# Test.net
KiCad netlist of a schematic drawn in EAGLE
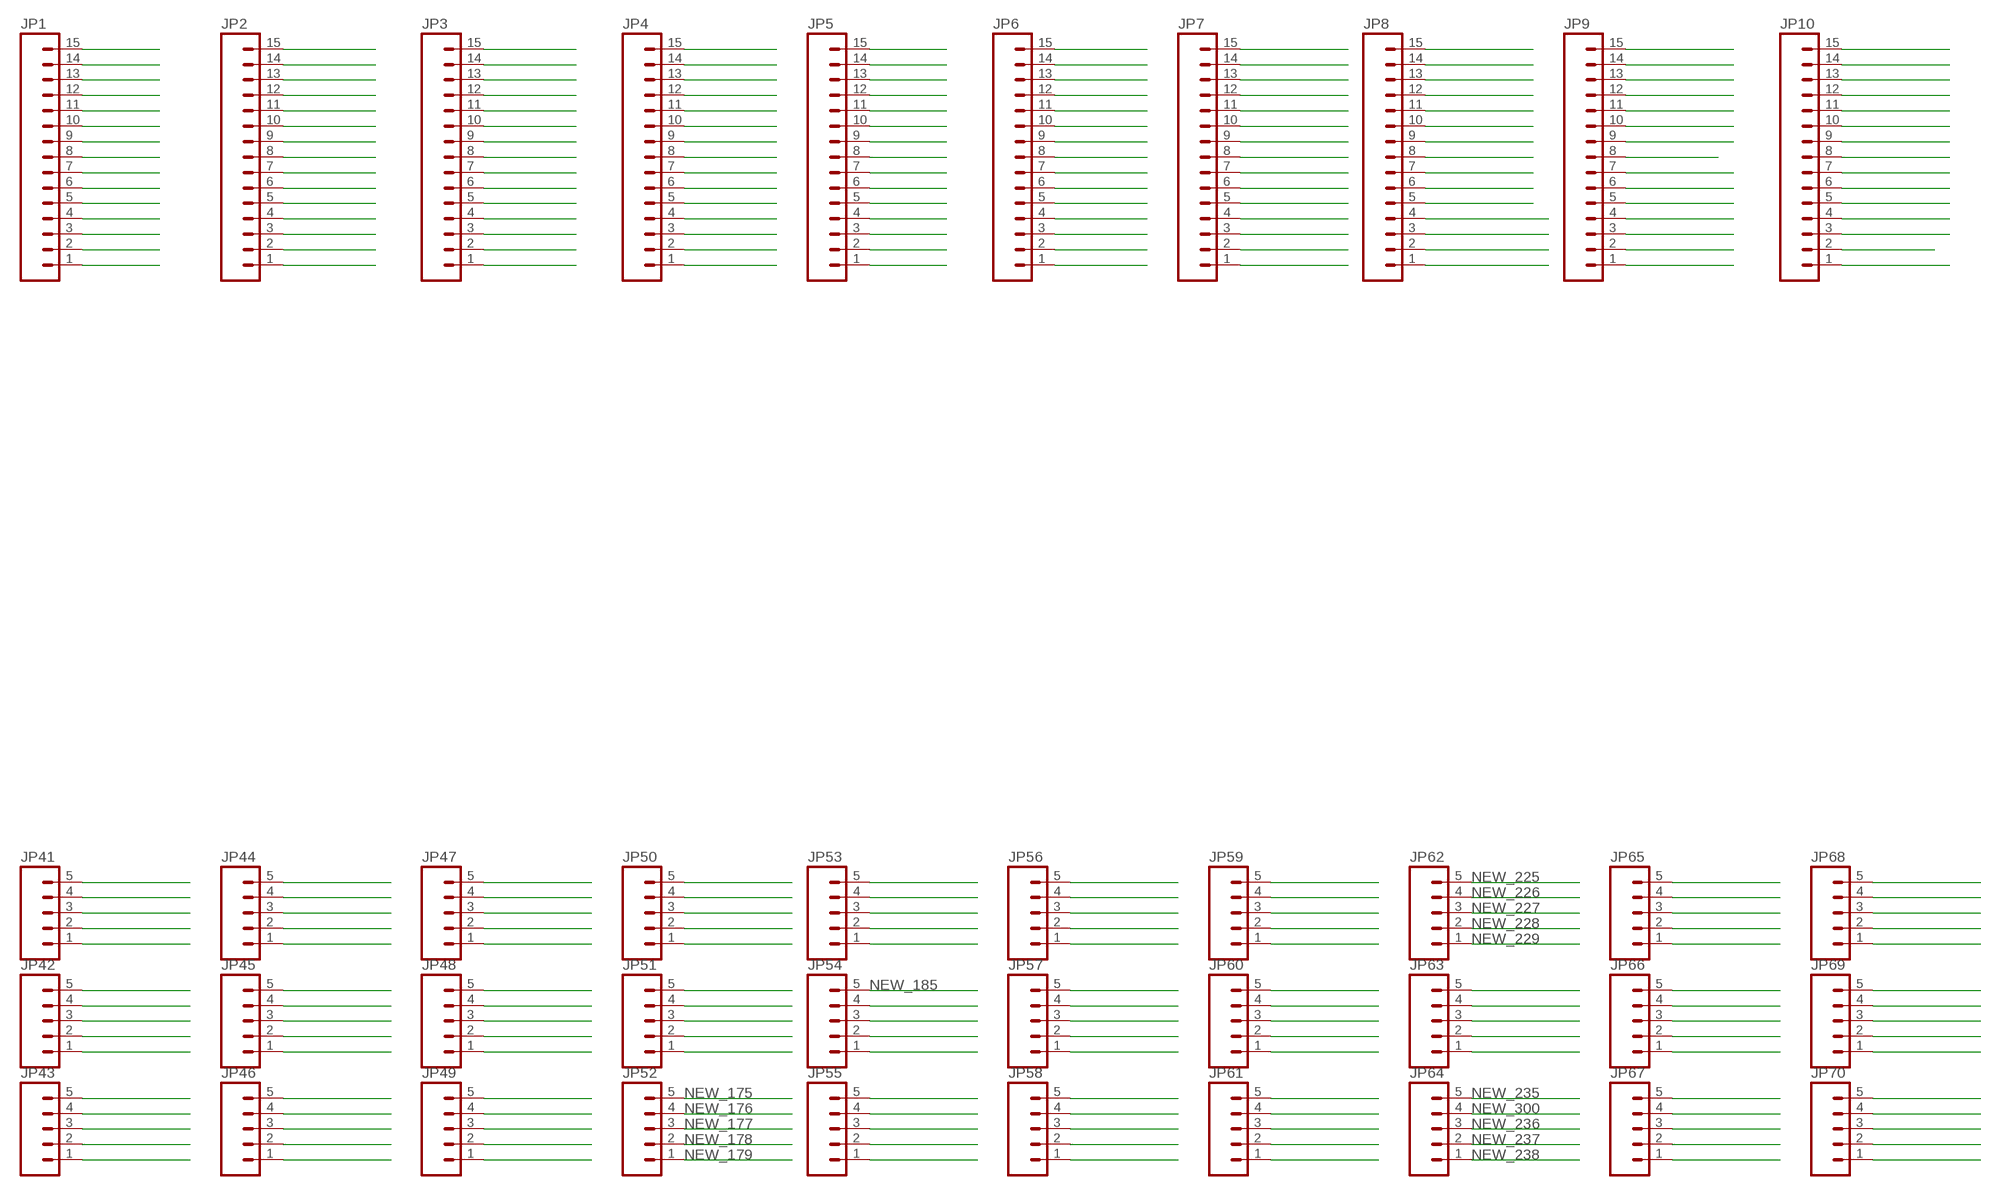
[diagram p0: schematic, sheet 1, part 1 of 2]
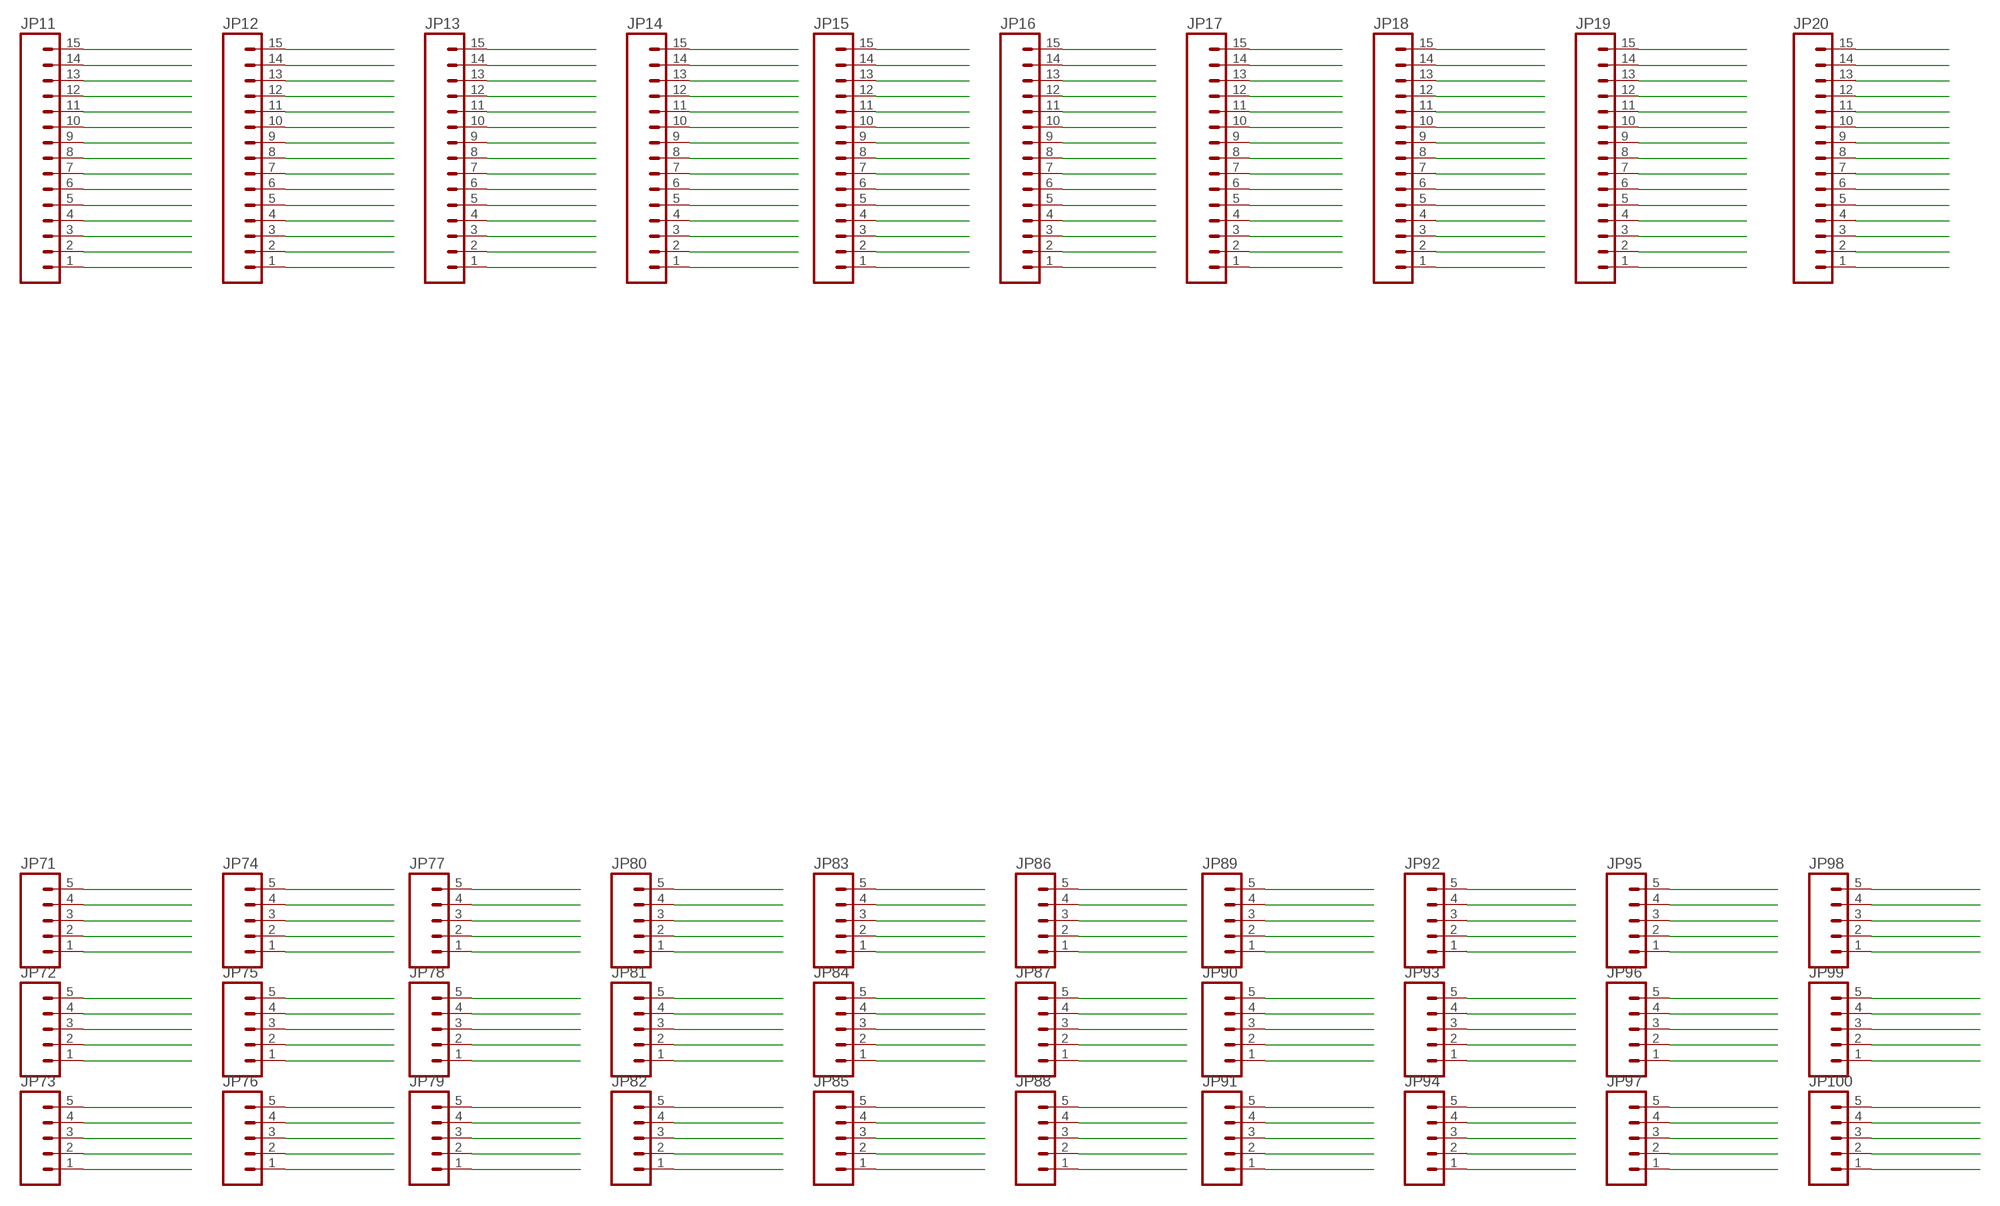
[diagram p1: schematic, sheet 1, part 2 of 2]

(export (version "E")
  (design (tool "Eeschema 10.0.6"))
  (components
    (comp (ref "JP1")
      (value "M15")
      (footprint "eagle-import:1X15")
      (libsource (lib "eagle-import") (part "M15"))
    )
    (comp (ref "JP2")
      (value "M15")
      (footprint "eagle-import:1X15")
      (libsource (lib "eagle-import") (part "M15"))
    )
    (comp (ref "JP3")
      (value "M15")
      (footprint "eagle-import:1X15")
      (libsource (lib "eagle-import") (part "M15"))
    )
    (comp (ref "JP4")
      (value "M15")
      (footprint "eagle-import:1X15")
      (libsource (lib "eagle-import") (part "M15"))
    )
    (comp (ref "JP5")
      (value "M15")
      (footprint "eagle-import:1X15")
      (libsource (lib "eagle-import") (part "M15"))
    )
    (comp (ref "JP6")
      (value "M15")
      (footprint "eagle-import:1X15")
      (libsource (lib "eagle-import") (part "M15"))
    )
    (comp (ref "JP7")
      (value "M15")
      (footprint "eagle-import:1X15")
      (libsource (lib "eagle-import") (part "M15"))
    )
    (comp (ref "JP8")
      (value "M15")
      (footprint "eagle-import:1X15")
      (libsource (lib "eagle-import") (part "M15"))
    )
    (comp (ref "JP9")
      (value "M15")
      (footprint "eagle-import:1X15")
      (libsource (lib "eagle-import") (part "M15"))
    )
    (comp (ref "JP10")
      (value "M15")
      (footprint "eagle-import:1X15")
      (libsource (lib "eagle-import") (part "M15"))
    )
    (comp (ref "JP11")
      (value "M15")
      (footprint "eagle-import:1X15")
      (libsource (lib "eagle-import") (part "M15"))
    )
    (comp (ref "JP12")
      (value "M15")
      (footprint "eagle-import:1X15")
      (libsource (lib "eagle-import") (part "M15"))
    )
    (comp (ref "JP13")
      (value "M15")
      (footprint "eagle-import:1X15")
      (libsource (lib "eagle-import") (part "M15"))
    )
    (comp (ref "JP14")
      (value "M15")
      (footprint "eagle-import:1X15")
      (libsource (lib "eagle-import") (part "M15"))
    )
    (comp (ref "JP15")
      (value "M15")
      (footprint "eagle-import:1X15")
      (libsource (lib "eagle-import") (part "M15"))
    )
    (comp (ref "JP16")
      (value "M15")
      (footprint "eagle-import:1X15")
      (libsource (lib "eagle-import") (part "M15"))
    )
    (comp (ref "JP17")
      (value "M15")
      (footprint "eagle-import:1X15")
      (libsource (lib "eagle-import") (part "M15"))
    )
    (comp (ref "JP18")
      (value "M15")
      (footprint "eagle-import:1X15")
      (libsource (lib "eagle-import") (part "M15"))
    )
    (comp (ref "JP19")
      (value "M15")
      (footprint "eagle-import:1X15")
      (libsource (lib "eagle-import") (part "M15"))
    )
    (comp (ref "JP20")
      (value "M15")
      (footprint "eagle-import:1X15")
      (libsource (lib "eagle-import") (part "M15"))
    )
    (comp (ref "JP41")
      (value "M051.27MM")
      (footprint "eagle-import:1X05-1.27MM")
      (libsource (lib "eagle-import") (part "M051.27MM"))
    )
    (comp (ref "JP42")
      (value "M051.27MM")
      (footprint "eagle-import:1X05-1.27MM")
      (libsource (lib "eagle-import") (part "M051.27MM"))
    )
    (comp (ref "JP43")
      (value "M051.27MM")
      (footprint "eagle-import:1X05-1.27MM")
      (libsource (lib "eagle-import") (part "M051.27MM"))
    )
    (comp (ref "JP44")
      (value "M051.27MM")
      (footprint "eagle-import:1X05-1.27MM")
      (libsource (lib "eagle-import") (part "M051.27MM"))
    )
    (comp (ref "JP45")
      (value "M051.27MM")
      (footprint "eagle-import:1X05-1.27MM")
      (libsource (lib "eagle-import") (part "M051.27MM"))
    )
    (comp (ref "JP46")
      (value "M051.27MM")
      (footprint "eagle-import:1X05-1.27MM")
      (libsource (lib "eagle-import") (part "M051.27MM"))
    )
    (comp (ref "JP47")
      (value "M051.27MM")
      (footprint "eagle-import:1X05-1.27MM")
      (libsource (lib "eagle-import") (part "M051.27MM"))
    )
    (comp (ref "JP48")
      (value "M051.27MM")
      (footprint "eagle-import:1X05-1.27MM")
      (libsource (lib "eagle-import") (part "M051.27MM"))
    )
    (comp (ref "JP49")
      (value "M051.27MM")
      (footprint "eagle-import:1X05-1.27MM")
      (libsource (lib "eagle-import") (part "M051.27MM"))
    )
    (comp (ref "JP50")
      (value "M051.27MM")
      (footprint "eagle-import:1X05-1.27MM")
      (libsource (lib "eagle-import") (part "M051.27MM"))
    )
    (comp (ref "JP51")
      (value "M051.27MM")
      (footprint "eagle-import:1X05-1.27MM")
      (libsource (lib "eagle-import") (part "M051.27MM"))
    )
    (comp (ref "JP52")
      (value "M051.27MM")
      (footprint "eagle-import:1X05-1.27MM")
      (libsource (lib "eagle-import") (part "M051.27MM"))
    )
    (comp (ref "JP53")
      (value "M051.27MM")
      (footprint "eagle-import:1X05-1.27MM")
      (libsource (lib "eagle-import") (part "M051.27MM"))
    )
    (comp (ref "JP54")
      (value "M051.27MM")
      (footprint "eagle-import:1X05-1.27MM")
      (libsource (lib "eagle-import") (part "M051.27MM"))
    )
    (comp (ref "JP55")
      (value "M051.27MM")
      (footprint "eagle-import:1X05-1.27MM")
      (libsource (lib "eagle-import") (part "M051.27MM"))
    )
    (comp (ref "JP56")
      (value "M051.27MM")
      (footprint "eagle-import:1X05-1.27MM")
      (libsource (lib "eagle-import") (part "M051.27MM"))
    )
    (comp (ref "JP57")
      (value "M051.27MM")
      (footprint "eagle-import:1X05-1.27MM")
      (libsource (lib "eagle-import") (part "M051.27MM"))
    )
    (comp (ref "JP58")
      (value "M051.27MM")
      (footprint "eagle-import:1X05-1.27MM")
      (libsource (lib "eagle-import") (part "M051.27MM"))
    )
    (comp (ref "JP59")
      (value "M051.27MM")
      (footprint "eagle-import:1X05-1.27MM")
      (libsource (lib "eagle-import") (part "M051.27MM"))
    )
    (comp (ref "JP60")
      (value "M051.27MM")
      (footprint "eagle-import:1X05-1.27MM")
      (libsource (lib "eagle-import") (part "M051.27MM"))
    )
    (comp (ref "JP61")
      (value "M051.27MM")
      (footprint "eagle-import:1X05-1.27MM")
      (libsource (lib "eagle-import") (part "M051.27MM"))
    )
    (comp (ref "JP62")
      (value "M051.27MM")
      (footprint "eagle-import:1X05-1.27MM")
      (libsource (lib "eagle-import") (part "M051.27MM"))
    )
    (comp (ref "JP63")
      (value "M051.27MM")
      (footprint "eagle-import:1X05-1.27MM")
      (libsource (lib "eagle-import") (part "M051.27MM"))
    )
    (comp (ref "JP64")
      (value "M051.27MM")
      (footprint "eagle-import:1X05-1.27MM")
      (libsource (lib "eagle-import") (part "M051.27MM"))
    )
    (comp (ref "JP65")
      (value "M051.27MM")
      (footprint "eagle-import:1X05-1.27MM")
      (libsource (lib "eagle-import") (part "M051.27MM"))
    )
    (comp (ref "JP66")
      (value "M051.27MM")
      (footprint "eagle-import:1X05-1.27MM")
      (libsource (lib "eagle-import") (part "M051.27MM"))
    )
    (comp (ref "JP67")
      (value "M051.27MM")
      (footprint "eagle-import:1X05-1.27MM")
      (libsource (lib "eagle-import") (part "M051.27MM"))
    )
    (comp (ref "JP68")
      (value "M051.27MM")
      (footprint "eagle-import:1X05-1.27MM")
      (libsource (lib "eagle-import") (part "M051.27MM"))
    )
    (comp (ref "JP69")
      (value "M051.27MM")
      (footprint "eagle-import:1X05-1.27MM")
      (libsource (lib "eagle-import") (part "M051.27MM"))
    )
    (comp (ref "JP70")
      (value "M051.27MM")
      (footprint "eagle-import:1X05-1.27MM")
      (libsource (lib "eagle-import") (part "M051.27MM"))
    )
    (comp (ref "JP71")
      (value "M051.27MM")
      (footprint "eagle-import:1X05-1.27MM")
      (libsource (lib "eagle-import") (part "M051.27MM"))
    )
    (comp (ref "JP72")
      (value "M051.27MM")
      (footprint "eagle-import:1X05-1.27MM")
      (libsource (lib "eagle-import") (part "M051.27MM"))
    )
    (comp (ref "JP73")
      (value "M051.27MM")
      (footprint "eagle-import:1X05-1.27MM")
      (libsource (lib "eagle-import") (part "M051.27MM"))
    )
    (comp (ref "JP74")
      (value "M051.27MM")
      (footprint "eagle-import:1X05-1.27MM")
      (libsource (lib "eagle-import") (part "M051.27MM"))
    )
    (comp (ref "JP75")
      (value "M051.27MM")
      (footprint "eagle-import:1X05-1.27MM")
      (libsource (lib "eagle-import") (part "M051.27MM"))
    )
    (comp (ref "JP76")
      (value "M051.27MM")
      (footprint "eagle-import:1X05-1.27MM")
      (libsource (lib "eagle-import") (part "M051.27MM"))
    )
    (comp (ref "JP77")
      (value "M051.27MM")
      (footprint "eagle-import:1X05-1.27MM")
      (libsource (lib "eagle-import") (part "M051.27MM"))
    )
    (comp (ref "JP78")
      (value "M051.27MM")
      (footprint "eagle-import:1X05-1.27MM")
      (libsource (lib "eagle-import") (part "M051.27MM"))
    )
    (comp (ref "JP79")
      (value "M051.27MM")
      (footprint "eagle-import:1X05-1.27MM")
      (libsource (lib "eagle-import") (part "M051.27MM"))
    )
    (comp (ref "JP80")
      (value "M051.27MM")
      (footprint "eagle-import:1X05-1.27MM")
      (libsource (lib "eagle-import") (part "M051.27MM"))
    )
    (comp (ref "JP81")
      (value "M051.27MM")
      (footprint "eagle-import:1X05-1.27MM")
      (libsource (lib "eagle-import") (part "M051.27MM"))
    )
    (comp (ref "JP82")
      (value "M051.27MM")
      (footprint "eagle-import:1X05-1.27MM")
      (libsource (lib "eagle-import") (part "M051.27MM"))
    )
    (comp (ref "JP83")
      (value "M051.27MM")
      (footprint "eagle-import:1X05-1.27MM")
      (libsource (lib "eagle-import") (part "M051.27MM"))
    )
    (comp (ref "JP84")
      (value "M051.27MM")
      (footprint "eagle-import:1X05-1.27MM")
      (libsource (lib "eagle-import") (part "M051.27MM"))
    )
    (comp (ref "JP85")
      (value "M051.27MM")
      (footprint "eagle-import:1X05-1.27MM")
      (libsource (lib "eagle-import") (part "M051.27MM"))
    )
    (comp (ref "JP86")
      (value "M051.27MM")
      (footprint "eagle-import:1X05-1.27MM")
      (libsource (lib "eagle-import") (part "M051.27MM"))
    )
    (comp (ref "JP87")
      (value "M051.27MM")
      (footprint "eagle-import:1X05-1.27MM")
      (libsource (lib "eagle-import") (part "M051.27MM"))
    )
    (comp (ref "JP88")
      (value "M051.27MM")
      (footprint "eagle-import:1X05-1.27MM")
      (libsource (lib "eagle-import") (part "M051.27MM"))
    )
    (comp (ref "JP89")
      (value "M051.27MM")
      (footprint "eagle-import:1X05-1.27MM")
      (libsource (lib "eagle-import") (part "M051.27MM"))
    )
    (comp (ref "JP90")
      (value "M051.27MM")
      (footprint "eagle-import:1X05-1.27MM")
      (libsource (lib "eagle-import") (part "M051.27MM"))
    )
    (comp (ref "JP91")
      (value "M051.27MM")
      (footprint "eagle-import:1X05-1.27MM")
      (libsource (lib "eagle-import") (part "M051.27MM"))
    )
    (comp (ref "JP92")
      (value "M051.27MM")
      (footprint "eagle-import:1X05-1.27MM")
      (libsource (lib "eagle-import") (part "M051.27MM"))
    )
    (comp (ref "JP93")
      (value "M051.27MM")
      (footprint "eagle-import:1X05-1.27MM")
      (libsource (lib "eagle-import") (part "M051.27MM"))
    )
    (comp (ref "JP94")
      (value "M051.27MM")
      (footprint "eagle-import:1X05-1.27MM")
      (libsource (lib "eagle-import") (part "M051.27MM"))
    )
    (comp (ref "JP95")
      (value "M051.27MM")
      (footprint "eagle-import:1X05-1.27MM")
      (libsource (lib "eagle-import") (part "M051.27MM"))
    )
    (comp (ref "JP96")
      (value "M051.27MM")
      (footprint "eagle-import:1X05-1.27MM")
      (libsource (lib "eagle-import") (part "M051.27MM"))
    )
    (comp (ref "JP97")
      (value "M051.27MM")
      (footprint "eagle-import:1X05-1.27MM")
      (libsource (lib "eagle-import") (part "M051.27MM"))
    )
    (comp (ref "JP98")
      (value "M051.27MM")
      (footprint "eagle-import:1X05-1.27MM")
      (libsource (lib "eagle-import") (part "M051.27MM"))
    )
    (comp (ref "JP99")
      (value "M051.27MM")
      (footprint "eagle-import:1X05-1.27MM")
      (libsource (lib "eagle-import") (part "M051.27MM"))
    )
    (comp (ref "JP100")
      (value "M051.27MM")
      (footprint "eagle-import:1X05-1.27MM")
      (libsource (lib "eagle-import") (part "M051.27MM"))
    )
  )
  (nets
    (net (code "1") (name "/NEW_0") (class "Default")
      (node (ref "JP65") (pin "5") (pinfunction "5_5") (pintype "passive"))
      (node (ref "JP7") (pin "3") (pinfunction "3_3") (pintype "passive"))
    )
    (net (code "2") (name "/NEW_1") (class "Default")
      (node (ref "JP65") (pin "4") (pinfunction "4_4") (pintype "passive"))
      (node (ref "JP7") (pin "2") (pinfunction "2_2") (pintype "passive"))
    )
    (net (code "3") (name "/NEW_2") (class "Default")
      (node (ref "JP65") (pin "3") (pinfunction "3_3") (pintype "passive"))
      (node (ref "JP8") (pin "2") (pinfunction "2_2") (pintype "passive"))
    )
    (net (code "4") (name "/NEW_3") (class "Default")
      (node (ref "JP65") (pin "2") (pinfunction "2_2") (pintype "passive"))
      (node (ref "JP7") (pin "1") (pinfunction "1_1") (pintype "passive"))
    )
    (net (code "5") (name "/NEW_4") (class "Default")
      (node (ref "JP65") (pin "1") (pinfunction "1_1") (pintype "passive"))
      (node (ref "JP8") (pin "1") (pinfunction "1_1") (pintype "passive"))
    )
    (net (code "6") (name "/NEW_5") (class "Default")
      (node (ref "JP66") (pin "5") (pinfunction "5_5") (pintype "passive"))
      (node (ref "JP7") (pin "5") (pinfunction "5_5") (pintype "passive"))
    )
    (net (code "7") (name "/NEW_6") (class "Default")
      (node (ref "JP66") (pin "4") (pinfunction "4_4") (pintype "passive"))
      (node (ref "JP8") (pin "5") (pinfunction "5_5") (pintype "passive"))
    )
    (net (code "8") (name "/NEW_7") (class "Default")
      (node (ref "JP66") (pin "3") (pinfunction "3_3") (pintype "passive"))
      (node (ref "JP7") (pin "4") (pinfunction "4_4") (pintype "passive"))
    )
    (net (code "9") (name "/NEW_8") (class "Default")
      (node (ref "JP66") (pin "2") (pinfunction "2_2") (pintype "passive"))
      (node (ref "JP8") (pin "4") (pinfunction "4_4") (pintype "passive"))
    )
    (net (code "10") (name "/NEW_9") (class "Default")
      (node (ref "JP66") (pin "1") (pinfunction "1_1") (pintype "passive"))
      (node (ref "JP8") (pin "3") (pinfunction "3_3") (pintype "passive"))
    )
    (net (code "11") (name "/NEW_10") (class "Default")
      (node (ref "JP67") (pin "5") (pinfunction "5_5") (pintype "passive"))
      (node (ref "JP7") (pin "8") (pinfunction "8_8") (pintype "passive"))
    )
    (net (code "12") (name "/NEW_11") (class "Default")
      (node (ref "JP67") (pin "4") (pinfunction "4_4") (pintype "passive"))
      (node (ref "JP7") (pin "7") (pinfunction "7_7") (pintype "passive"))
    )
    (net (code "13") (name "/NEW_12") (class "Default")
      (node (ref "JP67") (pin "3") (pinfunction "3_3") (pintype "passive"))
      (node (ref "JP8") (pin "7") (pinfunction "7_7") (pintype "passive"))
    )
    (net (code "14") (name "/NEW_13") (class "Default")
      (node (ref "JP67") (pin "2") (pinfunction "2_2") (pintype "passive"))
      (node (ref "JP7") (pin "6") (pinfunction "6_6") (pintype "passive"))
    )
    (net (code "15") (name "/NEW_14") (class "Default")
      (node (ref "JP67") (pin "1") (pinfunction "1_1") (pintype "passive"))
      (node (ref "JP8") (pin "6") (pinfunction "6_6") (pintype "passive"))
    )
    (net (code "16") (name "/NEW_15") (class "Default")
      (node (ref "JP68") (pin "5") (pinfunction "5_5") (pintype "passive"))
      (node (ref "JP7") (pin "10") (pinfunction "10_10") (pintype "passive"))
    )
    (net (code "17") (name "/NEW_16") (class "Default")
      (node (ref "JP68") (pin "4") (pinfunction "4_4") (pintype "passive"))
      (node (ref "JP8") (pin "10") (pinfunction "10_10") (pintype "passive"))
    )
    (net (code "18") (name "/NEW_17") (class "Default")
      (node (ref "JP68") (pin "3") (pinfunction "3_3") (pintype "passive"))
      (node (ref "JP7") (pin "9") (pinfunction "9_9") (pintype "passive"))
    )
    (net (code "19") (name "/NEW_18") (class "Default")
      (node (ref "JP68") (pin "2") (pinfunction "2_2") (pintype "passive"))
      (node (ref "JP8") (pin "9") (pinfunction "9_9") (pintype "passive"))
    )
    (net (code "20") (name "/NEW_19") (class "Default")
      (node (ref "JP68") (pin "1") (pinfunction "1_1") (pintype "passive"))
      (node (ref "JP8") (pin "8") (pinfunction "8_8") (pintype "passive"))
    )
    (net (code "21") (name "/NEW_20") (class "Default")
      (node (ref "JP69") (pin "5") (pinfunction "5_5") (pintype "passive"))
      (node (ref "JP7") (pin "13") (pinfunction "13_13") (pintype "passive"))
    )
    (net (code "22") (name "/NEW_21") (class "Default")
      (node (ref "JP69") (pin "4") (pinfunction "4_4") (pintype "passive"))
      (node (ref "JP7") (pin "12") (pinfunction "12_12") (pintype "passive"))
    )
    (net (code "23") (name "/NEW_22") (class "Default")
      (node (ref "JP69") (pin "3") (pinfunction "3_3") (pintype "passive"))
      (node (ref "JP8") (pin "12") (pinfunction "12_12") (pintype "passive"))
    )
    (net (code "24") (name "/NEW_23") (class "Default")
      (node (ref "JP69") (pin "2") (pinfunction "2_2") (pintype "passive"))
      (node (ref "JP7") (pin "11") (pinfunction "11_11") (pintype "passive"))
    )
    (net (code "25") (name "/NEW_24") (class "Default")
      (node (ref "JP69") (pin "1") (pinfunction "1_1") (pintype "passive"))
      (node (ref "JP8") (pin "11") (pinfunction "11_11") (pintype "passive"))
    )
    (net (code "26") (name "/NEW_25") (class "Default")
      (node (ref "JP7") (pin "15") (pinfunction "15_15") (pintype "passive"))
      (node (ref "JP70") (pin "5") (pinfunction "5_5") (pintype "passive"))
    )
    (net (code "27") (name "/NEW_26") (class "Default")
      (node (ref "JP70") (pin "4") (pinfunction "4_4") (pintype "passive"))
      (node (ref "JP8") (pin "15") (pinfunction "15_15") (pintype "passive"))
    )
    (net (code "28") (name "/NEW_27") (class "Default")
      (node (ref "JP7") (pin "14") (pinfunction "14_14") (pintype "passive"))
      (node (ref "JP70") (pin "3") (pinfunction "3_3") (pintype "passive"))
    )
    (net (code "29") (name "/NEW_28") (class "Default")
      (node (ref "JP70") (pin "2") (pinfunction "2_2") (pintype "passive"))
      (node (ref "JP8") (pin "14") (pinfunction "14_14") (pintype "passive"))
    )
    (net (code "30") (name "/NEW_29") (class "Default")
      (node (ref "JP70") (pin "1") (pinfunction "1_1") (pintype "passive"))
      (node (ref "JP8") (pin "13") (pinfunction "13_13") (pintype "passive"))
    )
    (net (code "31") (name "/NEW_30") (class "Default")
      (node (ref "JP17") (pin "3") (pinfunction "3_3") (pintype "passive"))
      (node (ref "JP71") (pin "5") (pinfunction "5_5") (pintype "passive"))
    )
    (net (code "32") (name "/NEW_31") (class "Default")
      (node (ref "JP17") (pin "2") (pinfunction "2_2") (pintype "passive"))
      (node (ref "JP71") (pin "4") (pinfunction "4_4") (pintype "passive"))
    )
    (net (code "33") (name "/NEW_32") (class "Default")
      (node (ref "JP18") (pin "2") (pinfunction "2_2") (pintype "passive"))
      (node (ref "JP71") (pin "3") (pinfunction "3_3") (pintype "passive"))
    )
    (net (code "34") (name "/NEW_33") (class "Default")
      (node (ref "JP17") (pin "1") (pinfunction "1_1") (pintype "passive"))
      (node (ref "JP71") (pin "2") (pinfunction "2_2") (pintype "passive"))
    )
    (net (code "35") (name "/NEW_34") (class "Default")
      (node (ref "JP18") (pin "1") (pinfunction "1_1") (pintype "passive"))
      (node (ref "JP71") (pin "1") (pinfunction "1_1") (pintype "passive"))
    )
    (net (code "36") (name "/NEW_35") (class "Default")
      (node (ref "JP17") (pin "5") (pinfunction "5_5") (pintype "passive"))
      (node (ref "JP72") (pin "5") (pinfunction "5_5") (pintype "passive"))
    )
    (net (code "37") (name "/NEW_36") (class "Default")
      (node (ref "JP18") (pin "5") (pinfunction "5_5") (pintype "passive"))
      (node (ref "JP72") (pin "4") (pinfunction "4_4") (pintype "passive"))
    )
    (net (code "38") (name "/NEW_37") (class "Default")
      (node (ref "JP17") (pin "4") (pinfunction "4_4") (pintype "passive"))
      (node (ref "JP72") (pin "3") (pinfunction "3_3") (pintype "passive"))
    )
    (net (code "39") (name "/NEW_38") (class "Default")
      (node (ref "JP18") (pin "4") (pinfunction "4_4") (pintype "passive"))
      (node (ref "JP72") (pin "2") (pinfunction "2_2") (pintype "passive"))
    )
    (net (code "40") (name "/NEW_39") (class "Default")
      (node (ref "JP18") (pin "3") (pinfunction "3_3") (pintype "passive"))
      (node (ref "JP72") (pin "1") (pinfunction "1_1") (pintype "passive"))
    )
    (net (code "41") (name "/NEW_40") (class "Default")
      (node (ref "JP17") (pin "8") (pinfunction "8_8") (pintype "passive"))
      (node (ref "JP73") (pin "5") (pinfunction "5_5") (pintype "passive"))
    )
    (net (code "42") (name "/NEW_41") (class "Default")
      (node (ref "JP17") (pin "7") (pinfunction "7_7") (pintype "passive"))
      (node (ref "JP73") (pin "4") (pinfunction "4_4") (pintype "passive"))
    )
    (net (code "43") (name "/NEW_42") (class "Default")
      (node (ref "JP18") (pin "7") (pinfunction "7_7") (pintype "passive"))
      (node (ref "JP73") (pin "3") (pinfunction "3_3") (pintype "passive"))
    )
    (net (code "44") (name "/NEW_43") (class "Default")
      (node (ref "JP17") (pin "6") (pinfunction "6_6") (pintype "passive"))
      (node (ref "JP73") (pin "2") (pinfunction "2_2") (pintype "passive"))
    )
    (net (code "45") (name "/NEW_44") (class "Default")
      (node (ref "JP18") (pin "6") (pinfunction "6_6") (pintype "passive"))
      (node (ref "JP73") (pin "1") (pinfunction "1_1") (pintype "passive"))
    )
    (net (code "46") (name "/NEW_45") (class "Default")
      (node (ref "JP17") (pin "10") (pinfunction "10_10") (pintype "passive"))
      (node (ref "JP74") (pin "5") (pinfunction "5_5") (pintype "passive"))
    )
    (net (code "47") (name "/NEW_46") (class "Default")
      (node (ref "JP18") (pin "10") (pinfunction "10_10") (pintype "passive"))
      (node (ref "JP74") (pin "4") (pinfunction "4_4") (pintype "passive"))
    )
    (net (code "48") (name "/NEW_47") (class "Default")
      (node (ref "JP17") (pin "9") (pinfunction "9_9") (pintype "passive"))
      (node (ref "JP74") (pin "3") (pinfunction "3_3") (pintype "passive"))
    )
    (net (code "49") (name "/NEW_48") (class "Default")
      (node (ref "JP18") (pin "9") (pinfunction "9_9") (pintype "passive"))
      (node (ref "JP74") (pin "2") (pinfunction "2_2") (pintype "passive"))
    )
    (net (code "50") (name "/NEW_49") (class "Default")
      (node (ref "JP18") (pin "8") (pinfunction "8_8") (pintype "passive"))
      (node (ref "JP74") (pin "1") (pinfunction "1_1") (pintype "passive"))
    )
    (net (code "51") (name "/NEW_50") (class "Default")
      (node (ref "JP17") (pin "13") (pinfunction "13_13") (pintype "passive"))
      (node (ref "JP75") (pin "5") (pinfunction "5_5") (pintype "passive"))
    )
    (net (code "52") (name "/NEW_51") (class "Default")
      (node (ref "JP17") (pin "12") (pinfunction "12_12") (pintype "passive"))
      (node (ref "JP75") (pin "4") (pinfunction "4_4") (pintype "passive"))
    )
    (net (code "53") (name "/NEW_52") (class "Default")
      (node (ref "JP18") (pin "12") (pinfunction "12_12") (pintype "passive"))
      (node (ref "JP75") (pin "3") (pinfunction "3_3") (pintype "passive"))
    )
    (net (code "54") (name "/NEW_53") (class "Default")
      (node (ref "JP17") (pin "11") (pinfunction "11_11") (pintype "passive"))
      (node (ref "JP75") (pin "2") (pinfunction "2_2") (pintype "passive"))
    )
    (net (code "55") (name "/NEW_54") (class "Default")
      (node (ref "JP18") (pin "11") (pinfunction "11_11") (pintype "passive"))
      (node (ref "JP75") (pin "1") (pinfunction "1_1") (pintype "passive"))
    )
    (net (code "56") (name "/NEW_55") (class "Default")
      (node (ref "JP17") (pin "15") (pinfunction "15_15") (pintype "passive"))
      (node (ref "JP76") (pin "5") (pinfunction "5_5") (pintype "passive"))
    )
    (net (code "57") (name "/NEW_56") (class "Default")
      (node (ref "JP18") (pin "15") (pinfunction "15_15") (pintype "passive"))
      (node (ref "JP76") (pin "4") (pinfunction "4_4") (pintype "passive"))
    )
    (net (code "58") (name "/NEW_57") (class "Default")
      (node (ref "JP17") (pin "14") (pinfunction "14_14") (pintype "passive"))
      (node (ref "JP76") (pin "3") (pinfunction "3_3") (pintype "passive"))
    )
    (net (code "59") (name "/NEW_58") (class "Default")
      (node (ref "JP18") (pin "14") (pinfunction "14_14") (pintype "passive"))
      (node (ref "JP76") (pin "2") (pinfunction "2_2") (pintype "passive"))
    )
    (net (code "60") (name "/NEW_59") (class "Default")
      (node (ref "JP18") (pin "13") (pinfunction "13_13") (pintype "passive"))
      (node (ref "JP76") (pin "1") (pinfunction "1_1") (pintype "passive"))
    )
    (net (code "61") (name "/NEW_60") (class "Default")
      (node (ref "JP77") (pin "5") (pinfunction "5_5") (pintype "passive"))
      (node (ref "JP9") (pin "3") (pinfunction "3_3") (pintype "passive"))
    )
    (net (code "62") (name "/NEW_61") (class "Default")
      (node (ref "JP77") (pin "4") (pinfunction "4_4") (pintype "passive"))
      (node (ref "JP9") (pin "2") (pinfunction "2_2") (pintype "passive"))
    )
    (net (code "63") (name "/NEW_62") (class "Default")
      (node (ref "JP10") (pin "2") (pinfunction "2_2") (pintype "passive"))
      (node (ref "JP77") (pin "3") (pinfunction "3_3") (pintype "passive"))
    )
    (net (code "64") (name "/NEW_63") (class "Default")
      (node (ref "JP77") (pin "2") (pinfunction "2_2") (pintype "passive"))
      (node (ref "JP9") (pin "1") (pinfunction "1_1") (pintype "passive"))
    )
    (net (code "65") (name "/NEW_64") (class "Default")
      (node (ref "JP10") (pin "1") (pinfunction "1_1") (pintype "passive"))
      (node (ref "JP77") (pin "1") (pinfunction "1_1") (pintype "passive"))
    )
    (net (code "66") (name "/NEW_65") (class "Default")
      (node (ref "JP78") (pin "5") (pinfunction "5_5") (pintype "passive"))
      (node (ref "JP9") (pin "5") (pinfunction "5_5") (pintype "passive"))
    )
    (net (code "67") (name "/NEW_66") (class "Default")
      (node (ref "JP10") (pin "5") (pinfunction "5_5") (pintype "passive"))
      (node (ref "JP78") (pin "4") (pinfunction "4_4") (pintype "passive"))
    )
    (net (code "68") (name "/NEW_67") (class "Default")
      (node (ref "JP78") (pin "3") (pinfunction "3_3") (pintype "passive"))
      (node (ref "JP9") (pin "4") (pinfunction "4_4") (pintype "passive"))
    )
    (net (code "69") (name "/NEW_68") (class "Default")
      (node (ref "JP10") (pin "4") (pinfunction "4_4") (pintype "passive"))
      (node (ref "JP78") (pin "2") (pinfunction "2_2") (pintype "passive"))
    )
    (net (code "70") (name "/NEW_69") (class "Default")
      (node (ref "JP10") (pin "3") (pinfunction "3_3") (pintype "passive"))
      (node (ref "JP78") (pin "1") (pinfunction "1_1") (pintype "passive"))
    )
    (net (code "71") (name "/NEW_70") (class "Default")
      (node (ref "JP79") (pin "5") (pinfunction "5_5") (pintype "passive"))
      (node (ref "JP9") (pin "8") (pinfunction "8_8") (pintype "passive"))
    )
    (net (code "72") (name "/NEW_71") (class "Default")
      (node (ref "JP79") (pin "4") (pinfunction "4_4") (pintype "passive"))
      (node (ref "JP9") (pin "7") (pinfunction "7_7") (pintype "passive"))
    )
    (net (code "73") (name "/NEW_72") (class "Default")
      (node (ref "JP10") (pin "7") (pinfunction "7_7") (pintype "passive"))
      (node (ref "JP79") (pin "3") (pinfunction "3_3") (pintype "passive"))
    )
    (net (code "74") (name "/NEW_73") (class "Default")
      (node (ref "JP79") (pin "2") (pinfunction "2_2") (pintype "passive"))
      (node (ref "JP9") (pin "6") (pinfunction "6_6") (pintype "passive"))
    )
    (net (code "75") (name "/NEW_74") (class "Default")
      (node (ref "JP10") (pin "6") (pinfunction "6_6") (pintype "passive"))
      (node (ref "JP79") (pin "1") (pinfunction "1_1") (pintype "passive"))
    )
    (net (code "76") (name "/NEW_75") (class "Default")
      (node (ref "JP80") (pin "5") (pinfunction "5_5") (pintype "passive"))
      (node (ref "JP9") (pin "10") (pinfunction "10_10") (pintype "passive"))
    )
    (net (code "77") (name "/NEW_76") (class "Default")
      (node (ref "JP10") (pin "10") (pinfunction "10_10") (pintype "passive"))
      (node (ref "JP80") (pin "4") (pinfunction "4_4") (pintype "passive"))
    )
    (net (code "78") (name "/NEW_77") (class "Default")
      (node (ref "JP80") (pin "3") (pinfunction "3_3") (pintype "passive"))
      (node (ref "JP9") (pin "9") (pinfunction "9_9") (pintype "passive"))
    )
    (net (code "79") (name "/NEW_78") (class "Default")
      (node (ref "JP10") (pin "9") (pinfunction "9_9") (pintype "passive"))
      (node (ref "JP80") (pin "2") (pinfunction "2_2") (pintype "passive"))
    )
    (net (code "80") (name "/NEW_79") (class "Default")
      (node (ref "JP10") (pin "8") (pinfunction "8_8") (pintype "passive"))
      (node (ref "JP80") (pin "1") (pinfunction "1_1") (pintype "passive"))
    )
    (net (code "81") (name "/NEW_80") (class "Default")
      (node (ref "JP81") (pin "5") (pinfunction "5_5") (pintype "passive"))
      (node (ref "JP9") (pin "13") (pinfunction "13_13") (pintype "passive"))
    )
    (net (code "82") (name "/NEW_81") (class "Default")
      (node (ref "JP81") (pin "4") (pinfunction "4_4") (pintype "passive"))
      (node (ref "JP9") (pin "12") (pinfunction "12_12") (pintype "passive"))
    )
    (net (code "83") (name "/NEW_82") (class "Default")
      (node (ref "JP10") (pin "12") (pinfunction "12_12") (pintype "passive"))
      (node (ref "JP81") (pin "3") (pinfunction "3_3") (pintype "passive"))
    )
    (net (code "84") (name "/NEW_83") (class "Default")
      (node (ref "JP81") (pin "2") (pinfunction "2_2") (pintype "passive"))
      (node (ref "JP9") (pin "11") (pinfunction "11_11") (pintype "passive"))
    )
    (net (code "85") (name "/NEW_84") (class "Default")
      (node (ref "JP10") (pin "11") (pinfunction "11_11") (pintype "passive"))
      (node (ref "JP81") (pin "1") (pinfunction "1_1") (pintype "passive"))
    )
    (net (code "86") (name "/NEW_85") (class "Default")
      (node (ref "JP82") (pin "5") (pinfunction "5_5") (pintype "passive"))
      (node (ref "JP9") (pin "15") (pinfunction "15_15") (pintype "passive"))
    )
    (net (code "87") (name "/NEW_86") (class "Default")
      (node (ref "JP10") (pin "15") (pinfunction "15_15") (pintype "passive"))
      (node (ref "JP82") (pin "4") (pinfunction "4_4") (pintype "passive"))
    )
    (net (code "88") (name "/NEW_87") (class "Default")
      (node (ref "JP82") (pin "3") (pinfunction "3_3") (pintype "passive"))
      (node (ref "JP9") (pin "14") (pinfunction "14_14") (pintype "passive"))
    )
    (net (code "89") (name "/NEW_88") (class "Default")
      (node (ref "JP10") (pin "14") (pinfunction "14_14") (pintype "passive"))
      (node (ref "JP82") (pin "2") (pinfunction "2_2") (pintype "passive"))
    )
    (net (code "90") (name "/NEW_89") (class "Default")
      (node (ref "JP10") (pin "13") (pinfunction "13_13") (pintype "passive"))
      (node (ref "JP82") (pin "1") (pinfunction "1_1") (pintype "passive"))
    )
    (net (code "91") (name "/NEW_90") (class "Default")
      (node (ref "JP19") (pin "3") (pinfunction "3_3") (pintype "passive"))
      (node (ref "JP83") (pin "5") (pinfunction "5_5") (pintype "passive"))
    )
    (net (code "92") (name "/NEW_91") (class "Default")
      (node (ref "JP19") (pin "2") (pinfunction "2_2") (pintype "passive"))
      (node (ref "JP83") (pin "4") (pinfunction "4_4") (pintype "passive"))
    )
    (net (code "93") (name "/NEW_92") (class "Default")
      (node (ref "JP20") (pin "2") (pinfunction "2_2") (pintype "passive"))
      (node (ref "JP83") (pin "3") (pinfunction "3_3") (pintype "passive"))
    )
    (net (code "94") (name "/NEW_93") (class "Default")
      (node (ref "JP19") (pin "1") (pinfunction "1_1") (pintype "passive"))
      (node (ref "JP83") (pin "2") (pinfunction "2_2") (pintype "passive"))
    )
    (net (code "95") (name "/NEW_94") (class "Default")
      (node (ref "JP20") (pin "1") (pinfunction "1_1") (pintype "passive"))
      (node (ref "JP83") (pin "1") (pinfunction "1_1") (pintype "passive"))
    )
    (net (code "96") (name "/NEW_95") (class "Default")
      (node (ref "JP19") (pin "5") (pinfunction "5_5") (pintype "passive"))
      (node (ref "JP84") (pin "5") (pinfunction "5_5") (pintype "passive"))
    )
    (net (code "97") (name "/NEW_96") (class "Default")
      (node (ref "JP20") (pin "5") (pinfunction "5_5") (pintype "passive"))
      (node (ref "JP84") (pin "4") (pinfunction "4_4") (pintype "passive"))
    )
    (net (code "98") (name "/NEW_97") (class "Default")
      (node (ref "JP19") (pin "4") (pinfunction "4_4") (pintype "passive"))
      (node (ref "JP84") (pin "3") (pinfunction "3_3") (pintype "passive"))
    )
    (net (code "99") (name "/NEW_98") (class "Default")
      (node (ref "JP20") (pin "4") (pinfunction "4_4") (pintype "passive"))
      (node (ref "JP84") (pin "2") (pinfunction "2_2") (pintype "passive"))
    )
    (net (code "100") (name "/NEW_99") (class "Default")
      (node (ref "JP20") (pin "3") (pinfunction "3_3") (pintype "passive"))
      (node (ref "JP84") (pin "1") (pinfunction "1_1") (pintype "passive"))
    )
    (net (code "101") (name "/NEW_100") (class "Default")
      (node (ref "JP19") (pin "8") (pinfunction "8_8") (pintype "passive"))
      (node (ref "JP85") (pin "5") (pinfunction "5_5") (pintype "passive"))
    )
    (net (code "102") (name "/NEW_101") (class "Default")
      (node (ref "JP19") (pin "7") (pinfunction "7_7") (pintype "passive"))
      (node (ref "JP85") (pin "4") (pinfunction "4_4") (pintype "passive"))
    )
    (net (code "103") (name "/NEW_102") (class "Default")
      (node (ref "JP20") (pin "7") (pinfunction "7_7") (pintype "passive"))
      (node (ref "JP85") (pin "3") (pinfunction "3_3") (pintype "passive"))
    )
    (net (code "104") (name "/NEW_103") (class "Default")
      (node (ref "JP19") (pin "6") (pinfunction "6_6") (pintype "passive"))
      (node (ref "JP85") (pin "2") (pinfunction "2_2") (pintype "passive"))
    )
    (net (code "105") (name "/NEW_104") (class "Default")
      (node (ref "JP20") (pin "6") (pinfunction "6_6") (pintype "passive"))
      (node (ref "JP85") (pin "1") (pinfunction "1_1") (pintype "passive"))
    )
    (net (code "106") (name "/NEW_105") (class "Default")
      (node (ref "JP19") (pin "10") (pinfunction "10_10") (pintype "passive"))
      (node (ref "JP86") (pin "5") (pinfunction "5_5") (pintype "passive"))
    )
    (net (code "107") (name "/NEW_106") (class "Default")
      (node (ref "JP20") (pin "10") (pinfunction "10_10") (pintype "passive"))
      (node (ref "JP86") (pin "4") (pinfunction "4_4") (pintype "passive"))
    )
    (net (code "108") (name "/NEW_107") (class "Default")
      (node (ref "JP19") (pin "9") (pinfunction "9_9") (pintype "passive"))
      (node (ref "JP86") (pin "3") (pinfunction "3_3") (pintype "passive"))
    )
    (net (code "109") (name "/NEW_108") (class "Default")
      (node (ref "JP20") (pin "9") (pinfunction "9_9") (pintype "passive"))
      (node (ref "JP86") (pin "2") (pinfunction "2_2") (pintype "passive"))
    )
    (net (code "110") (name "/NEW_109") (class "Default")
      (node (ref "JP20") (pin "8") (pinfunction "8_8") (pintype "passive"))
      (node (ref "JP86") (pin "1") (pinfunction "1_1") (pintype "passive"))
    )
    (net (code "111") (name "/NEW_110") (class "Default")
      (node (ref "JP19") (pin "13") (pinfunction "13_13") (pintype "passive"))
      (node (ref "JP87") (pin "5") (pinfunction "5_5") (pintype "passive"))
    )
    (net (code "112") (name "/NEW_111") (class "Default")
      (node (ref "JP19") (pin "12") (pinfunction "12_12") (pintype "passive"))
      (node (ref "JP87") (pin "4") (pinfunction "4_4") (pintype "passive"))
    )
    (net (code "113") (name "/NEW_112") (class "Default")
      (node (ref "JP20") (pin "12") (pinfunction "12_12") (pintype "passive"))
      (node (ref "JP87") (pin "3") (pinfunction "3_3") (pintype "passive"))
    )
    (net (code "114") (name "/NEW_113") (class "Default")
      (node (ref "JP19") (pin "11") (pinfunction "11_11") (pintype "passive"))
      (node (ref "JP87") (pin "2") (pinfunction "2_2") (pintype "passive"))
    )
    (net (code "115") (name "/NEW_114") (class "Default")
      (node (ref "JP20") (pin "11") (pinfunction "11_11") (pintype "passive"))
      (node (ref "JP87") (pin "1") (pinfunction "1_1") (pintype "passive"))
    )
    (net (code "116") (name "/NEW_115") (class "Default")
      (node (ref "JP19") (pin "15") (pinfunction "15_15") (pintype "passive"))
      (node (ref "JP88") (pin "5") (pinfunction "5_5") (pintype "passive"))
    )
    (net (code "117") (name "/NEW_116") (class "Default")
      (node (ref "JP20") (pin "15") (pinfunction "15_15") (pintype "passive"))
      (node (ref "JP88") (pin "4") (pinfunction "4_4") (pintype "passive"))
    )
    (net (code "118") (name "/NEW_117") (class "Default")
      (node (ref "JP19") (pin "14") (pinfunction "14_14") (pintype "passive"))
      (node (ref "JP88") (pin "3") (pinfunction "3_3") (pintype "passive"))
    )
    (net (code "119") (name "/NEW_118") (class "Default")
      (node (ref "JP20") (pin "14") (pinfunction "14_14") (pintype "passive"))
      (node (ref "JP88") (pin "2") (pinfunction "2_2") (pintype "passive"))
    )
    (net (code "120") (name "/NEW_119") (class "Default")
      (node (ref "JP20") (pin "13") (pinfunction "13_13") (pintype "passive"))
      (node (ref "JP88") (pin "1") (pinfunction "1_1") (pintype "passive"))
    )
    (net (code "121") (name "/NEW_120") (class "Default")
      (node (ref "JP1") (pin "3") (pinfunction "3_3") (pintype "passive"))
      (node (ref "JP41") (pin "5") (pinfunction "5_5") (pintype "passive"))
    )
    (net (code "122") (name "/NEW_121") (class "Default")
      (node (ref "JP1") (pin "2") (pinfunction "2_2") (pintype "passive"))
      (node (ref "JP41") (pin "4") (pinfunction "4_4") (pintype "passive"))
    )
    (net (code "123") (name "/NEW_122") (class "Default")
      (node (ref "JP2") (pin "2") (pinfunction "2_2") (pintype "passive"))
      (node (ref "JP41") (pin "3") (pinfunction "3_3") (pintype "passive"))
    )
    (net (code "124") (name "/NEW_123") (class "Default")
      (node (ref "JP1") (pin "1") (pinfunction "1_1") (pintype "passive"))
      (node (ref "JP41") (pin "2") (pinfunction "2_2") (pintype "passive"))
    )
    (net (code "125") (name "/NEW_124") (class "Default")
      (node (ref "JP2") (pin "1") (pinfunction "1_1") (pintype "passive"))
      (node (ref "JP41") (pin "1") (pinfunction "1_1") (pintype "passive"))
    )
    (net (code "126") (name "/NEW_125") (class "Default")
      (node (ref "JP1") (pin "5") (pinfunction "5_5") (pintype "passive"))
      (node (ref "JP42") (pin "5") (pinfunction "5_5") (pintype "passive"))
    )
    (net (code "127") (name "/NEW_126") (class "Default")
      (node (ref "JP2") (pin "5") (pinfunction "5_5") (pintype "passive"))
      (node (ref "JP42") (pin "4") (pinfunction "4_4") (pintype "passive"))
    )
    (net (code "128") (name "/NEW_127") (class "Default")
      (node (ref "JP1") (pin "4") (pinfunction "4_4") (pintype "passive"))
      (node (ref "JP42") (pin "3") (pinfunction "3_3") (pintype "passive"))
    )
    (net (code "129") (name "/NEW_128") (class "Default")
      (node (ref "JP2") (pin "4") (pinfunction "4_4") (pintype "passive"))
      (node (ref "JP42") (pin "2") (pinfunction "2_2") (pintype "passive"))
    )
    (net (code "130") (name "/NEW_129") (class "Default")
      (node (ref "JP2") (pin "3") (pinfunction "3_3") (pintype "passive"))
      (node (ref "JP42") (pin "1") (pinfunction "1_1") (pintype "passive"))
    )
    (net (code "131") (name "/NEW_130") (class "Default")
      (node (ref "JP1") (pin "8") (pinfunction "8_8") (pintype "passive"))
      (node (ref "JP43") (pin "5") (pinfunction "5_5") (pintype "passive"))
    )
    (net (code "132") (name "/NEW_131") (class "Default")
      (node (ref "JP1") (pin "7") (pinfunction "7_7") (pintype "passive"))
      (node (ref "JP43") (pin "4") (pinfunction "4_4") (pintype "passive"))
    )
    (net (code "133") (name "/NEW_132") (class "Default")
      (node (ref "JP2") (pin "7") (pinfunction "7_7") (pintype "passive"))
      (node (ref "JP43") (pin "3") (pinfunction "3_3") (pintype "passive"))
    )
    (net (code "134") (name "/NEW_133") (class "Default")
      (node (ref "JP1") (pin "6") (pinfunction "6_6") (pintype "passive"))
      (node (ref "JP43") (pin "2") (pinfunction "2_2") (pintype "passive"))
    )
    (net (code "135") (name "/NEW_134") (class "Default")
      (node (ref "JP2") (pin "6") (pinfunction "6_6") (pintype "passive"))
      (node (ref "JP43") (pin "1") (pinfunction "1_1") (pintype "passive"))
    )
    (net (code "136") (name "/NEW_135") (class "Default")
      (node (ref "JP1") (pin "10") (pinfunction "10_10") (pintype "passive"))
      (node (ref "JP44") (pin "5") (pinfunction "5_5") (pintype "passive"))
    )
    (net (code "137") (name "/NEW_136") (class "Default")
      (node (ref "JP2") (pin "10") (pinfunction "10_10") (pintype "passive"))
      (node (ref "JP44") (pin "4") (pinfunction "4_4") (pintype "passive"))
    )
    (net (code "138") (name "/NEW_137") (class "Default")
      (node (ref "JP1") (pin "9") (pinfunction "9_9") (pintype "passive"))
      (node (ref "JP44") (pin "3") (pinfunction "3_3") (pintype "passive"))
    )
    (net (code "139") (name "/NEW_138") (class "Default")
      (node (ref "JP2") (pin "9") (pinfunction "9_9") (pintype "passive"))
      (node (ref "JP44") (pin "2") (pinfunction "2_2") (pintype "passive"))
    )
    (net (code "140") (name "/NEW_139") (class "Default")
      (node (ref "JP2") (pin "8") (pinfunction "8_8") (pintype "passive"))
      (node (ref "JP44") (pin "1") (pinfunction "1_1") (pintype "passive"))
    )
    (net (code "141") (name "/NEW_140") (class "Default")
      (node (ref "JP1") (pin "13") (pinfunction "13_13") (pintype "passive"))
      (node (ref "JP45") (pin "5") (pinfunction "5_5") (pintype "passive"))
    )
    (net (code "142") (name "/NEW_141") (class "Default")
      (node (ref "JP1") (pin "12") (pinfunction "12_12") (pintype "passive"))
      (node (ref "JP45") (pin "4") (pinfunction "4_4") (pintype "passive"))
    )
    (net (code "143") (name "/NEW_142") (class "Default")
      (node (ref "JP2") (pin "12") (pinfunction "12_12") (pintype "passive"))
      (node (ref "JP45") (pin "3") (pinfunction "3_3") (pintype "passive"))
    )
    (net (code "144") (name "/NEW_143") (class "Default")
      (node (ref "JP1") (pin "11") (pinfunction "11_11") (pintype "passive"))
      (node (ref "JP45") (pin "2") (pinfunction "2_2") (pintype "passive"))
    )
    (net (code "145") (name "/NEW_144") (class "Default")
      (node (ref "JP2") (pin "11") (pinfunction "11_11") (pintype "passive"))
      (node (ref "JP45") (pin "1") (pinfunction "1_1") (pintype "passive"))
    )
    (net (code "146") (name "/NEW_145") (class "Default")
      (node (ref "JP1") (pin "15") (pinfunction "15_15") (pintype "passive"))
      (node (ref "JP46") (pin "5") (pinfunction "5_5") (pintype "passive"))
    )
    (net (code "147") (name "/NEW_146") (class "Default")
      (node (ref "JP2") (pin "15") (pinfunction "15_15") (pintype "passive"))
      (node (ref "JP46") (pin "4") (pinfunction "4_4") (pintype "passive"))
    )
    (net (code "148") (name "/NEW_147") (class "Default")
      (node (ref "JP1") (pin "14") (pinfunction "14_14") (pintype "passive"))
      (node (ref "JP46") (pin "3") (pinfunction "3_3") (pintype "passive"))
    )
    (net (code "149") (name "/NEW_148") (class "Default")
      (node (ref "JP2") (pin "14") (pinfunction "14_14") (pintype "passive"))
      (node (ref "JP46") (pin "2") (pinfunction "2_2") (pintype "passive"))
    )
    (net (code "150") (name "/NEW_149") (class "Default")
      (node (ref "JP2") (pin "13") (pinfunction "13_13") (pintype "passive"))
      (node (ref "JP46") (pin "1") (pinfunction "1_1") (pintype "passive"))
    )
    (net (code "151") (name "/NEW_150") (class "Default")
      (node (ref "JP11") (pin "3") (pinfunction "3_3") (pintype "passive"))
      (node (ref "JP47") (pin "5") (pinfunction "5_5") (pintype "passive"))
    )
    (net (code "152") (name "/NEW_151") (class "Default")
      (node (ref "JP11") (pin "2") (pinfunction "2_2") (pintype "passive"))
      (node (ref "JP47") (pin "4") (pinfunction "4_4") (pintype "passive"))
    )
    (net (code "153") (name "/NEW_152") (class "Default")
      (node (ref "JP12") (pin "2") (pinfunction "2_2") (pintype "passive"))
      (node (ref "JP47") (pin "3") (pinfunction "3_3") (pintype "passive"))
    )
    (net (code "154") (name "/NEW_153") (class "Default")
      (node (ref "JP11") (pin "1") (pinfunction "1_1") (pintype "passive"))
      (node (ref "JP47") (pin "2") (pinfunction "2_2") (pintype "passive"))
    )
    (net (code "155") (name "/NEW_154") (class "Default")
      (node (ref "JP12") (pin "1") (pinfunction "1_1") (pintype "passive"))
      (node (ref "JP47") (pin "1") (pinfunction "1_1") (pintype "passive"))
    )
    (net (code "156") (name "/NEW_155") (class "Default")
      (node (ref "JP11") (pin "5") (pinfunction "5_5") (pintype "passive"))
      (node (ref "JP48") (pin "5") (pinfunction "5_5") (pintype "passive"))
    )
    (net (code "157") (name "/NEW_156") (class "Default")
      (node (ref "JP12") (pin "5") (pinfunction "5_5") (pintype "passive"))
      (node (ref "JP48") (pin "4") (pinfunction "4_4") (pintype "passive"))
    )
    (net (code "158") (name "/NEW_157") (class "Default")
      (node (ref "JP11") (pin "4") (pinfunction "4_4") (pintype "passive"))
      (node (ref "JP48") (pin "3") (pinfunction "3_3") (pintype "passive"))
    )
    (net (code "159") (name "/NEW_158") (class "Default")
      (node (ref "JP12") (pin "4") (pinfunction "4_4") (pintype "passive"))
      (node (ref "JP48") (pin "2") (pinfunction "2_2") (pintype "passive"))
    )
    (net (code "160") (name "/NEW_159") (class "Default")
      (node (ref "JP12") (pin "3") (pinfunction "3_3") (pintype "passive"))
      (node (ref "JP48") (pin "1") (pinfunction "1_1") (pintype "passive"))
    )
    (net (code "161") (name "/NEW_160") (class "Default")
      (node (ref "JP11") (pin "8") (pinfunction "8_8") (pintype "passive"))
      (node (ref "JP49") (pin "5") (pinfunction "5_5") (pintype "passive"))
    )
    (net (code "162") (name "/NEW_161") (class "Default")
      (node (ref "JP11") (pin "7") (pinfunction "7_7") (pintype "passive"))
      (node (ref "JP49") (pin "4") (pinfunction "4_4") (pintype "passive"))
    )
    (net (code "163") (name "/NEW_162") (class "Default")
      (node (ref "JP12") (pin "7") (pinfunction "7_7") (pintype "passive"))
      (node (ref "JP49") (pin "3") (pinfunction "3_3") (pintype "passive"))
    )
    (net (code "164") (name "/NEW_163") (class "Default")
      (node (ref "JP11") (pin "6") (pinfunction "6_6") (pintype "passive"))
      (node (ref "JP49") (pin "2") (pinfunction "2_2") (pintype "passive"))
    )
    (net (code "165") (name "/NEW_164") (class "Default")
      (node (ref "JP12") (pin "6") (pinfunction "6_6") (pintype "passive"))
      (node (ref "JP49") (pin "1") (pinfunction "1_1") (pintype "passive"))
    )
    (net (code "166") (name "/NEW_165") (class "Default")
      (node (ref "JP11") (pin "10") (pinfunction "10_10") (pintype "passive"))
      (node (ref "JP50") (pin "5") (pinfunction "5_5") (pintype "passive"))
    )
    (net (code "167") (name "/NEW_166") (class "Default")
      (node (ref "JP12") (pin "10") (pinfunction "10_10") (pintype "passive"))
      (node (ref "JP50") (pin "4") (pinfunction "4_4") (pintype "passive"))
    )
    (net (code "168") (name "/NEW_167") (class "Default")
      (node (ref "JP11") (pin "9") (pinfunction "9_9") (pintype "passive"))
      (node (ref "JP50") (pin "3") (pinfunction "3_3") (pintype "passive"))
    )
    (net (code "169") (name "/NEW_168") (class "Default")
      (node (ref "JP12") (pin "9") (pinfunction "9_9") (pintype "passive"))
      (node (ref "JP50") (pin "2") (pinfunction "2_2") (pintype "passive"))
    )
    (net (code "170") (name "/NEW_169") (class "Default")
      (node (ref "JP12") (pin "8") (pinfunction "8_8") (pintype "passive"))
      (node (ref "JP50") (pin "1") (pinfunction "1_1") (pintype "passive"))
    )
    (net (code "171") (name "/NEW_170") (class "Default")
      (node (ref "JP11") (pin "13") (pinfunction "13_13") (pintype "passive"))
      (node (ref "JP51") (pin "5") (pinfunction "5_5") (pintype "passive"))
    )
    (net (code "172") (name "/NEW_171") (class "Default")
      (node (ref "JP11") (pin "12") (pinfunction "12_12") (pintype "passive"))
      (node (ref "JP51") (pin "4") (pinfunction "4_4") (pintype "passive"))
    )
    (net (code "173") (name "/NEW_172") (class "Default")
      (node (ref "JP12") (pin "12") (pinfunction "12_12") (pintype "passive"))
      (node (ref "JP51") (pin "3") (pinfunction "3_3") (pintype "passive"))
    )
    (net (code "174") (name "/NEW_173") (class "Default")
      (node (ref "JP11") (pin "11") (pinfunction "11_11") (pintype "passive"))
      (node (ref "JP51") (pin "2") (pinfunction "2_2") (pintype "passive"))
    )
    (net (code "175") (name "/NEW_174") (class "Default")
      (node (ref "JP12") (pin "11") (pinfunction "11_11") (pintype "passive"))
      (node (ref "JP51") (pin "1") (pinfunction "1_1") (pintype "passive"))
    )
    (net (code "176") (name "/NEW_175") (class "Default")
      (node (ref "JP11") (pin "15") (pinfunction "15_15") (pintype "passive"))
      (node (ref "JP52") (pin "5") (pinfunction "5_5") (pintype "passive"))
    )
    (net (code "177") (name "/NEW_176") (class "Default")
      (node (ref "JP12") (pin "15") (pinfunction "15_15") (pintype "passive"))
      (node (ref "JP52") (pin "4") (pinfunction "4_4") (pintype "passive"))
    )
    (net (code "178") (name "/NEW_177") (class "Default")
      (node (ref "JP11") (pin "14") (pinfunction "14_14") (pintype "passive"))
      (node (ref "JP52") (pin "3") (pinfunction "3_3") (pintype "passive"))
    )
    (net (code "179") (name "/NEW_178") (class "Default")
      (node (ref "JP12") (pin "14") (pinfunction "14_14") (pintype "passive"))
      (node (ref "JP52") (pin "2") (pinfunction "2_2") (pintype "passive"))
    )
    (net (code "180") (name "/NEW_179") (class "Default")
      (node (ref "JP12") (pin "13") (pinfunction "13_13") (pintype "passive"))
      (node (ref "JP52") (pin "1") (pinfunction "1_1") (pintype "passive"))
    )
    (net (code "181") (name "/NEW_180") (class "Default")
      (node (ref "JP3") (pin "3") (pinfunction "3_3") (pintype "passive"))
      (node (ref "JP53") (pin "5") (pinfunction "5_5") (pintype "passive"))
    )
    (net (code "182") (name "/NEW_181") (class "Default")
      (node (ref "JP3") (pin "2") (pinfunction "2_2") (pintype "passive"))
      (node (ref "JP53") (pin "4") (pinfunction "4_4") (pintype "passive"))
    )
    (net (code "183") (name "/NEW_182") (class "Default")
      (node (ref "JP4") (pin "2") (pinfunction "2_2") (pintype "passive"))
      (node (ref "JP53") (pin "3") (pinfunction "3_3") (pintype "passive"))
    )
    (net (code "184") (name "/NEW_183") (class "Default")
      (node (ref "JP3") (pin "1") (pinfunction "1_1") (pintype "passive"))
      (node (ref "JP53") (pin "2") (pinfunction "2_2") (pintype "passive"))
    )
    (net (code "185") (name "/NEW_184") (class "Default")
      (node (ref "JP4") (pin "1") (pinfunction "1_1") (pintype "passive"))
      (node (ref "JP53") (pin "1") (pinfunction "1_1") (pintype "passive"))
    )
    (net (code "186") (name "/NEW_185") (class "Default")
      (node (ref "JP3") (pin "5") (pinfunction "5_5") (pintype "passive"))
      (node (ref "JP54") (pin "5") (pinfunction "5_5") (pintype "passive"))
    )
    (net (code "187") (name "/NEW_186") (class "Default")
      (node (ref "JP4") (pin "5") (pinfunction "5_5") (pintype "passive"))
      (node (ref "JP54") (pin "4") (pinfunction "4_4") (pintype "passive"))
    )
    (net (code "188") (name "/NEW_187") (class "Default")
      (node (ref "JP3") (pin "4") (pinfunction "4_4") (pintype "passive"))
      (node (ref "JP54") (pin "3") (pinfunction "3_3") (pintype "passive"))
    )
    (net (code "189") (name "/NEW_188") (class "Default")
      (node (ref "JP4") (pin "4") (pinfunction "4_4") (pintype "passive"))
      (node (ref "JP54") (pin "2") (pinfunction "2_2") (pintype "passive"))
    )
    (net (code "190") (name "/NEW_189") (class "Default")
      (node (ref "JP4") (pin "3") (pinfunction "3_3") (pintype "passive"))
      (node (ref "JP54") (pin "1") (pinfunction "1_1") (pintype "passive"))
    )
    (net (code "191") (name "/NEW_190") (class "Default")
      (node (ref "JP3") (pin "8") (pinfunction "8_8") (pintype "passive"))
      (node (ref "JP55") (pin "5") (pinfunction "5_5") (pintype "passive"))
    )
    (net (code "192") (name "/NEW_191") (class "Default")
      (node (ref "JP3") (pin "7") (pinfunction "7_7") (pintype "passive"))
      (node (ref "JP55") (pin "4") (pinfunction "4_4") (pintype "passive"))
    )
    (net (code "193") (name "/NEW_192") (class "Default")
      (node (ref "JP4") (pin "7") (pinfunction "7_7") (pintype "passive"))
      (node (ref "JP55") (pin "3") (pinfunction "3_3") (pintype "passive"))
    )
    (net (code "194") (name "/NEW_193") (class "Default")
      (node (ref "JP3") (pin "6") (pinfunction "6_6") (pintype "passive"))
      (node (ref "JP55") (pin "2") (pinfunction "2_2") (pintype "passive"))
    )
    (net (code "195") (name "/NEW_194") (class "Default")
      (node (ref "JP4") (pin "6") (pinfunction "6_6") (pintype "passive"))
      (node (ref "JP55") (pin "1") (pinfunction "1_1") (pintype "passive"))
    )
    (net (code "196") (name "/NEW_195") (class "Default")
      (node (ref "JP3") (pin "10") (pinfunction "10_10") (pintype "passive"))
      (node (ref "JP56") (pin "5") (pinfunction "5_5") (pintype "passive"))
    )
    (net (code "197") (name "/NEW_196") (class "Default")
      (node (ref "JP4") (pin "10") (pinfunction "10_10") (pintype "passive"))
      (node (ref "JP56") (pin "4") (pinfunction "4_4") (pintype "passive"))
    )
    (net (code "198") (name "/NEW_197") (class "Default")
      (node (ref "JP3") (pin "9") (pinfunction "9_9") (pintype "passive"))
      (node (ref "JP56") (pin "3") (pinfunction "3_3") (pintype "passive"))
    )
    (net (code "199") (name "/NEW_198") (class "Default")
      (node (ref "JP4") (pin "9") (pinfunction "9_9") (pintype "passive"))
      (node (ref "JP56") (pin "2") (pinfunction "2_2") (pintype "passive"))
    )
    (net (code "200") (name "/NEW_199") (class "Default")
      (node (ref "JP4") (pin "8") (pinfunction "8_8") (pintype "passive"))
      (node (ref "JP56") (pin "1") (pinfunction "1_1") (pintype "passive"))
    )
    (net (code "201") (name "/NEW_200") (class "Default")
      (node (ref "JP3") (pin "13") (pinfunction "13_13") (pintype "passive"))
      (node (ref "JP57") (pin "5") (pinfunction "5_5") (pintype "passive"))
    )
    (net (code "202") (name "/NEW_201") (class "Default")
      (node (ref "JP3") (pin "12") (pinfunction "12_12") (pintype "passive"))
      (node (ref "JP57") (pin "4") (pinfunction "4_4") (pintype "passive"))
    )
    (net (code "203") (name "/NEW_202") (class "Default")
      (node (ref "JP4") (pin "12") (pinfunction "12_12") (pintype "passive"))
      (node (ref "JP57") (pin "3") (pinfunction "3_3") (pintype "passive"))
    )
    (net (code "204") (name "/NEW_203") (class "Default")
      (node (ref "JP3") (pin "11") (pinfunction "11_11") (pintype "passive"))
      (node (ref "JP57") (pin "2") (pinfunction "2_2") (pintype "passive"))
    )
    (net (code "205") (name "/NEW_204") (class "Default")
      (node (ref "JP4") (pin "11") (pinfunction "11_11") (pintype "passive"))
      (node (ref "JP57") (pin "1") (pinfunction "1_1") (pintype "passive"))
    )
    (net (code "206") (name "/NEW_205") (class "Default")
      (node (ref "JP3") (pin "15") (pinfunction "15_15") (pintype "passive"))
      (node (ref "JP58") (pin "5") (pinfunction "5_5") (pintype "passive"))
    )
    (net (code "207") (name "/NEW_206") (class "Default")
      (node (ref "JP4") (pin "15") (pinfunction "15_15") (pintype "passive"))
      (node (ref "JP58") (pin "4") (pinfunction "4_4") (pintype "passive"))
    )
    (net (code "208") (name "/NEW_207") (class "Default")
      (node (ref "JP3") (pin "14") (pinfunction "14_14") (pintype "passive"))
      (node (ref "JP58") (pin "3") (pinfunction "3_3") (pintype "passive"))
    )
    (net (code "209") (name "/NEW_208") (class "Default")
      (node (ref "JP4") (pin "14") (pinfunction "14_14") (pintype "passive"))
      (node (ref "JP58") (pin "2") (pinfunction "2_2") (pintype "passive"))
    )
    (net (code "210") (name "/NEW_209") (class "Default")
      (node (ref "JP4") (pin "13") (pinfunction "13_13") (pintype "passive"))
      (node (ref "JP58") (pin "1") (pinfunction "1_1") (pintype "passive"))
    )
    (net (code "211") (name "/NEW_210") (class "Default")
      (node (ref "JP13") (pin "3") (pinfunction "3_3") (pintype "passive"))
      (node (ref "JP59") (pin "5") (pinfunction "5_5") (pintype "passive"))
    )
    (net (code "212") (name "/NEW_211") (class "Default")
      (node (ref "JP13") (pin "2") (pinfunction "2_2") (pintype "passive"))
      (node (ref "JP59") (pin "4") (pinfunction "4_4") (pintype "passive"))
    )
    (net (code "213") (name "/NEW_212") (class "Default")
      (node (ref "JP14") (pin "2") (pinfunction "2_2") (pintype "passive"))
      (node (ref "JP59") (pin "3") (pinfunction "3_3") (pintype "passive"))
    )
    (net (code "214") (name "/NEW_213") (class "Default")
      (node (ref "JP13") (pin "1") (pinfunction "1_1") (pintype "passive"))
      (node (ref "JP59") (pin "2") (pinfunction "2_2") (pintype "passive"))
    )
    (net (code "215") (name "/NEW_214") (class "Default")
      (node (ref "JP14") (pin "1") (pinfunction "1_1") (pintype "passive"))
      (node (ref "JP59") (pin "1") (pinfunction "1_1") (pintype "passive"))
    )
    (net (code "216") (name "/NEW_215") (class "Default")
      (node (ref "JP13") (pin "5") (pinfunction "5_5") (pintype "passive"))
      (node (ref "JP60") (pin "5") (pinfunction "5_5") (pintype "passive"))
    )
    (net (code "217") (name "/NEW_216") (class "Default")
      (node (ref "JP14") (pin "5") (pinfunction "5_5") (pintype "passive"))
      (node (ref "JP60") (pin "4") (pinfunction "4_4") (pintype "passive"))
    )
    (net (code "218") (name "/NEW_217") (class "Default")
      (node (ref "JP13") (pin "4") (pinfunction "4_4") (pintype "passive"))
      (node (ref "JP60") (pin "3") (pinfunction "3_3") (pintype "passive"))
    )
    (net (code "219") (name "/NEW_218") (class "Default")
      (node (ref "JP14") (pin "4") (pinfunction "4_4") (pintype "passive"))
      (node (ref "JP60") (pin "2") (pinfunction "2_2") (pintype "passive"))
    )
    (net (code "220") (name "/NEW_219") (class "Default")
      (node (ref "JP14") (pin "3") (pinfunction "3_3") (pintype "passive"))
      (node (ref "JP60") (pin "1") (pinfunction "1_1") (pintype "passive"))
    )
    (net (code "221") (name "/NEW_220") (class "Default")
      (node (ref "JP13") (pin "8") (pinfunction "8_8") (pintype "passive"))
      (node (ref "JP61") (pin "5") (pinfunction "5_5") (pintype "passive"))
    )
    (net (code "222") (name "/NEW_221") (class "Default")
      (node (ref "JP13") (pin "7") (pinfunction "7_7") (pintype "passive"))
      (node (ref "JP61") (pin "4") (pinfunction "4_4") (pintype "passive"))
    )
    (net (code "223") (name "/NEW_222") (class "Default")
      (node (ref "JP14") (pin "7") (pinfunction "7_7") (pintype "passive"))
      (node (ref "JP61") (pin "3") (pinfunction "3_3") (pintype "passive"))
    )
    (net (code "224") (name "/NEW_223") (class "Default")
      (node (ref "JP13") (pin "6") (pinfunction "6_6") (pintype "passive"))
      (node (ref "JP61") (pin "2") (pinfunction "2_2") (pintype "passive"))
    )
    (net (code "225") (name "/NEW_224") (class "Default")
      (node (ref "JP14") (pin "6") (pinfunction "6_6") (pintype "passive"))
      (node (ref "JP61") (pin "1") (pinfunction "1_1") (pintype "passive"))
    )
    (net (code "226") (name "/NEW_225") (class "Default")
      (node (ref "JP13") (pin "10") (pinfunction "10_10") (pintype "passive"))
      (node (ref "JP62") (pin "5") (pinfunction "5_5") (pintype "passive"))
    )
    (net (code "227") (name "/NEW_226") (class "Default")
      (node (ref "JP14") (pin "10") (pinfunction "10_10") (pintype "passive"))
      (node (ref "JP62") (pin "4") (pinfunction "4_4") (pintype "passive"))
    )
    (net (code "228") (name "/NEW_227") (class "Default")
      (node (ref "JP13") (pin "9") (pinfunction "9_9") (pintype "passive"))
      (node (ref "JP62") (pin "3") (pinfunction "3_3") (pintype "passive"))
    )
    (net (code "229") (name "/NEW_228") (class "Default")
      (node (ref "JP14") (pin "9") (pinfunction "9_9") (pintype "passive"))
      (node (ref "JP62") (pin "2") (pinfunction "2_2") (pintype "passive"))
    )
    (net (code "230") (name "/NEW_229") (class "Default")
      (node (ref "JP14") (pin "8") (pinfunction "8_8") (pintype "passive"))
      (node (ref "JP62") (pin "1") (pinfunction "1_1") (pintype "passive"))
    )
    (net (code "231") (name "/NEW_230") (class "Default")
      (node (ref "JP13") (pin "13") (pinfunction "13_13") (pintype "passive"))
      (node (ref "JP63") (pin "5") (pinfunction "5_5") (pintype "passive"))
    )
    (net (code "232") (name "/NEW_231") (class "Default")
      (node (ref "JP13") (pin "12") (pinfunction "12_12") (pintype "passive"))
      (node (ref "JP63") (pin "4") (pinfunction "4_4") (pintype "passive"))
    )
    (net (code "233") (name "/NEW_232") (class "Default")
      (node (ref "JP14") (pin "12") (pinfunction "12_12") (pintype "passive"))
      (node (ref "JP63") (pin "3") (pinfunction "3_3") (pintype "passive"))
    )
    (net (code "234") (name "/NEW_233") (class "Default")
      (node (ref "JP13") (pin "11") (pinfunction "11_11") (pintype "passive"))
      (node (ref "JP63") (pin "2") (pinfunction "2_2") (pintype "passive"))
    )
    (net (code "235") (name "/NEW_234") (class "Default")
      (node (ref "JP14") (pin "11") (pinfunction "11_11") (pintype "passive"))
      (node (ref "JP63") (pin "1") (pinfunction "1_1") (pintype "passive"))
    )
    (net (code "236") (name "/NEW_235") (class "Default")
      (node (ref "JP14") (pin "15") (pinfunction "15_15") (pintype "passive"))
      (node (ref "JP64") (pin "5") (pinfunction "5_5") (pintype "passive"))
    )
    (net (code "237") (name "/NEW_236") (class "Default")
      (node (ref "JP13") (pin "14") (pinfunction "14_14") (pintype "passive"))
      (node (ref "JP64") (pin "3") (pinfunction "3_3") (pintype "passive"))
    )
    (net (code "238") (name "/NEW_237") (class "Default")
      (node (ref "JP14") (pin "14") (pinfunction "14_14") (pintype "passive"))
      (node (ref "JP64") (pin "2") (pinfunction "2_2") (pintype "passive"))
    )
    (net (code "239") (name "/NEW_238") (class "Default")
      (node (ref "JP14") (pin "13") (pinfunction "13_13") (pintype "passive"))
      (node (ref "JP64") (pin "1") (pinfunction "1_1") (pintype "passive"))
    )
    (net (code "240") (name "/NEW_239") (class "Default")
      (node (ref "JP5") (pin "5") (pinfunction "5_5") (pintype "passive"))
      (node (ref "JP89") (pin "5") (pinfunction "5_5") (pintype "passive"))
    )
    (net (code "241") (name "/NEW_240") (class "Default")
      (node (ref "JP5") (pin "4") (pinfunction "4_4") (pintype "passive"))
      (node (ref "JP89") (pin "4") (pinfunction "4_4") (pintype "passive"))
    )
    (net (code "242") (name "/NEW_241") (class "Default")
      (node (ref "JP5") (pin "3") (pinfunction "3_3") (pintype "passive"))
      (node (ref "JP89") (pin "3") (pinfunction "3_3") (pintype "passive"))
    )
    (net (code "243") (name "/NEW_242") (class "Default")
      (node (ref "JP5") (pin "2") (pinfunction "2_2") (pintype "passive"))
      (node (ref "JP89") (pin "2") (pinfunction "2_2") (pintype "passive"))
    )
    (net (code "244") (name "/NEW_243") (class "Default")
      (node (ref "JP5") (pin "1") (pinfunction "1_1") (pintype "passive"))
      (node (ref "JP89") (pin "1") (pinfunction "1_1") (pintype "passive"))
    )
    (net (code "245") (name "/NEW_244") (class "Default")
      (node (ref "JP5") (pin "10") (pinfunction "10_10") (pintype "passive"))
      (node (ref "JP90") (pin "5") (pinfunction "5_5") (pintype "passive"))
    )
    (net (code "246") (name "/NEW_245") (class "Default")
      (node (ref "JP5") (pin "9") (pinfunction "9_9") (pintype "passive"))
      (node (ref "JP90") (pin "4") (pinfunction "4_4") (pintype "passive"))
    )
    (net (code "247") (name "/NEW_246") (class "Default")
      (node (ref "JP5") (pin "8") (pinfunction "8_8") (pintype "passive"))
      (node (ref "JP90") (pin "3") (pinfunction "3_3") (pintype "passive"))
    )
    (net (code "248") (name "/NEW_247") (class "Default")
      (node (ref "JP5") (pin "7") (pinfunction "7_7") (pintype "passive"))
      (node (ref "JP90") (pin "2") (pinfunction "2_2") (pintype "passive"))
    )
    (net (code "249") (name "/NEW_248") (class "Default")
      (node (ref "JP5") (pin "6") (pinfunction "6_6") (pintype "passive"))
      (node (ref "JP90") (pin "1") (pinfunction "1_1") (pintype "passive"))
    )
    (net (code "250") (name "/NEW_249") (class "Default")
      (node (ref "JP5") (pin "15") (pinfunction "15_15") (pintype "passive"))
      (node (ref "JP91") (pin "5") (pinfunction "5_5") (pintype "passive"))
    )
    (net (code "251") (name "/NEW_250") (class "Default")
      (node (ref "JP5") (pin "14") (pinfunction "14_14") (pintype "passive"))
      (node (ref "JP91") (pin "4") (pinfunction "4_4") (pintype "passive"))
    )
    (net (code "252") (name "/NEW_251") (class "Default")
      (node (ref "JP5") (pin "13") (pinfunction "13_13") (pintype "passive"))
      (node (ref "JP91") (pin "3") (pinfunction "3_3") (pintype "passive"))
    )
    (net (code "253") (name "/NEW_252") (class "Default")
      (node (ref "JP5") (pin "12") (pinfunction "12_12") (pintype "passive"))
      (node (ref "JP91") (pin "2") (pinfunction "2_2") (pintype "passive"))
    )
    (net (code "254") (name "/NEW_253") (class "Default")
      (node (ref "JP5") (pin "11") (pinfunction "11_11") (pintype "passive"))
      (node (ref "JP91") (pin "1") (pinfunction "1_1") (pintype "passive"))
    )
    (net (code "255") (name "/NEW_254") (class "Default")
      (node (ref "JP15") (pin "5") (pinfunction "5_5") (pintype "passive"))
      (node (ref "JP92") (pin "5") (pinfunction "5_5") (pintype "passive"))
    )
    (net (code "256") (name "/NEW_255") (class "Default")
      (node (ref "JP15") (pin "4") (pinfunction "4_4") (pintype "passive"))
      (node (ref "JP92") (pin "4") (pinfunction "4_4") (pintype "passive"))
    )
    (net (code "257") (name "/NEW_256") (class "Default")
      (node (ref "JP15") (pin "3") (pinfunction "3_3") (pintype "passive"))
      (node (ref "JP92") (pin "3") (pinfunction "3_3") (pintype "passive"))
    )
    (net (code "258") (name "/NEW_257") (class "Default")
      (node (ref "JP15") (pin "2") (pinfunction "2_2") (pintype "passive"))
      (node (ref "JP92") (pin "2") (pinfunction "2_2") (pintype "passive"))
    )
    (net (code "259") (name "/NEW_258") (class "Default")
      (node (ref "JP15") (pin "1") (pinfunction "1_1") (pintype "passive"))
      (node (ref "JP92") (pin "1") (pinfunction "1_1") (pintype "passive"))
    )
    (net (code "260") (name "/NEW_259") (class "Default")
      (node (ref "JP15") (pin "11") (pinfunction "11_11") (pintype "passive"))
      (node (ref "JP97") (pin "5") (pinfunction "5_5") (pintype "passive"))
    )
    (net (code "261") (name "/NEW_260") (class "Default")
      (node (ref "JP15") (pin "12") (pinfunction "12_12") (pintype "passive"))
      (node (ref "JP97") (pin "4") (pinfunction "4_4") (pintype "passive"))
    )
    (net (code "262") (name "/NEW_261") (class "Default")
      (node (ref "JP15") (pin "13") (pinfunction "13_13") (pintype "passive"))
      (node (ref "JP97") (pin "3") (pinfunction "3_3") (pintype "passive"))
    )
    (net (code "263") (name "/NEW_262") (class "Default")
      (node (ref "JP15") (pin "14") (pinfunction "14_14") (pintype "passive"))
      (node (ref "JP97") (pin "2") (pinfunction "2_2") (pintype "passive"))
    )
    (net (code "264") (name "/NEW_263") (class "Default")
      (node (ref "JP15") (pin "15") (pinfunction "15_15") (pintype "passive"))
      (node (ref "JP97") (pin "1") (pinfunction "1_1") (pintype "passive"))
    )
    (net (code "265") (name "/NEW_264") (class "Default")
      (node (ref "JP15") (pin "6") (pinfunction "6_6") (pintype "passive"))
      (node (ref "JP98") (pin "5") (pinfunction "5_5") (pintype "passive"))
    )
    (net (code "266") (name "/NEW_265") (class "Default")
      (node (ref "JP15") (pin "7") (pinfunction "7_7") (pintype "passive"))
      (node (ref "JP98") (pin "4") (pinfunction "4_4") (pintype "passive"))
    )
    (net (code "267") (name "/NEW_266") (class "Default")
      (node (ref "JP15") (pin "8") (pinfunction "8_8") (pintype "passive"))
      (node (ref "JP98") (pin "3") (pinfunction "3_3") (pintype "passive"))
    )
    (net (code "268") (name "/NEW_267") (class "Default")
      (node (ref "JP15") (pin "9") (pinfunction "9_9") (pintype "passive"))
      (node (ref "JP98") (pin "2") (pinfunction "2_2") (pintype "passive"))
    )
    (net (code "269") (name "/NEW_268") (class "Default")
      (node (ref "JP15") (pin "10") (pinfunction "10_10") (pintype "passive"))
      (node (ref "JP98") (pin "1") (pinfunction "1_1") (pintype "passive"))
    )
    (net (code "270") (name "/NEW_269") (class "Default")
      (node (ref "JP16") (pin "1") (pinfunction "1_1") (pintype "passive"))
      (node (ref "JP93") (pin "5") (pinfunction "5_5") (pintype "passive"))
    )
    (net (code "271") (name "/NEW_270") (class "Default")
      (node (ref "JP16") (pin "2") (pinfunction "2_2") (pintype "passive"))
      (node (ref "JP93") (pin "4") (pinfunction "4_4") (pintype "passive"))
    )
    (net (code "272") (name "/NEW_271") (class "Default")
      (node (ref "JP16") (pin "3") (pinfunction "3_3") (pintype "passive"))
      (node (ref "JP93") (pin "3") (pinfunction "3_3") (pintype "passive"))
    )
    (net (code "273") (name "/NEW_272") (class "Default")
      (node (ref "JP16") (pin "4") (pinfunction "4_4") (pintype "passive"))
      (node (ref "JP93") (pin "2") (pinfunction "2_2") (pintype "passive"))
    )
    (net (code "274") (name "/NEW_273") (class "Default")
      (node (ref "JP16") (pin "5") (pinfunction "5_5") (pintype "passive"))
      (node (ref "JP93") (pin "1") (pinfunction "1_1") (pintype "passive"))
    )
    (net (code "275") (name "/NEW_274") (class "Default")
      (node (ref "JP6") (pin "11") (pinfunction "11_11") (pintype "passive"))
      (node (ref "JP94") (pin "5") (pinfunction "5_5") (pintype "passive"))
    )
    (net (code "276") (name "/NEW_275") (class "Default")
      (node (ref "JP6") (pin "12") (pinfunction "12_12") (pintype "passive"))
      (node (ref "JP94") (pin "4") (pinfunction "4_4") (pintype "passive"))
    )
    (net (code "277") (name "/NEW_276") (class "Default")
      (node (ref "JP6") (pin "13") (pinfunction "13_13") (pintype "passive"))
      (node (ref "JP94") (pin "3") (pinfunction "3_3") (pintype "passive"))
    )
    (net (code "278") (name "/NEW_277") (class "Default")
      (node (ref "JP6") (pin "14") (pinfunction "14_14") (pintype "passive"))
      (node (ref "JP94") (pin "2") (pinfunction "2_2") (pintype "passive"))
    )
    (net (code "279") (name "/NEW_278") (class "Default")
      (node (ref "JP6") (pin "15") (pinfunction "15_15") (pintype "passive"))
      (node (ref "JP94") (pin "1") (pinfunction "1_1") (pintype "passive"))
    )
    (net (code "280") (name "/NEW_279") (class "Default")
      (node (ref "JP6") (pin "6") (pinfunction "6_6") (pintype "passive"))
      (node (ref "JP95") (pin "5") (pinfunction "5_5") (pintype "passive"))
    )
    (net (code "281") (name "/NEW_280") (class "Default")
      (node (ref "JP6") (pin "7") (pinfunction "7_7") (pintype "passive"))
      (node (ref "JP95") (pin "4") (pinfunction "4_4") (pintype "passive"))
    )
    (net (code "282") (name "/NEW_281") (class "Default")
      (node (ref "JP6") (pin "8") (pinfunction "8_8") (pintype "passive"))
      (node (ref "JP95") (pin "3") (pinfunction "3_3") (pintype "passive"))
    )
    (net (code "283") (name "/NEW_282") (class "Default")
      (node (ref "JP6") (pin "9") (pinfunction "9_9") (pintype "passive"))
      (node (ref "JP95") (pin "2") (pinfunction "2_2") (pintype "passive"))
    )
    (net (code "284") (name "/NEW_283") (class "Default")
      (node (ref "JP6") (pin "10") (pinfunction "10_10") (pintype "passive"))
      (node (ref "JP95") (pin "1") (pinfunction "1_1") (pintype "passive"))
    )
    (net (code "285") (name "/NEW_284") (class "Default")
      (node (ref "JP6") (pin "1") (pinfunction "1_1") (pintype "passive"))
      (node (ref "JP96") (pin "5") (pinfunction "5_5") (pintype "passive"))
    )
    (net (code "286") (name "/NEW_285") (class "Default")
      (node (ref "JP6") (pin "2") (pinfunction "2_2") (pintype "passive"))
      (node (ref "JP96") (pin "4") (pinfunction "4_4") (pintype "passive"))
    )
    (net (code "287") (name "/NEW_286") (class "Default")
      (node (ref "JP6") (pin "3") (pinfunction "3_3") (pintype "passive"))
      (node (ref "JP96") (pin "3") (pinfunction "3_3") (pintype "passive"))
    )
    (net (code "288") (name "/NEW_287") (class "Default")
      (node (ref "JP6") (pin "4") (pinfunction "4_4") (pintype "passive"))
      (node (ref "JP96") (pin "2") (pinfunction "2_2") (pintype "passive"))
    )
    (net (code "289") (name "/NEW_288") (class "Default")
      (node (ref "JP6") (pin "5") (pinfunction "5_5") (pintype "passive"))
      (node (ref "JP96") (pin "1") (pinfunction "1_1") (pintype "passive"))
    )
    (net (code "290") (name "/NEW_289") (class "Default")
      (node (ref "JP16") (pin "10") (pinfunction "10_10") (pintype "passive"))
      (node (ref "JP99") (pin "5") (pinfunction "5_5") (pintype "passive"))
    )
    (net (code "291") (name "/NEW_290") (class "Default")
      (node (ref "JP16") (pin "9") (pinfunction "9_9") (pintype "passive"))
      (node (ref "JP99") (pin "4") (pinfunction "4_4") (pintype "passive"))
    )
    (net (code "292") (name "/NEW_291") (class "Default")
      (node (ref "JP16") (pin "8") (pinfunction "8_8") (pintype "passive"))
      (node (ref "JP99") (pin "3") (pinfunction "3_3") (pintype "passive"))
    )
    (net (code "293") (name "/NEW_292") (class "Default")
      (node (ref "JP16") (pin "7") (pinfunction "7_7") (pintype "passive"))
      (node (ref "JP99") (pin "2") (pinfunction "2_2") (pintype "passive"))
    )
    (net (code "294") (name "/NEW_293") (class "Default")
      (node (ref "JP16") (pin "6") (pinfunction "6_6") (pintype "passive"))
      (node (ref "JP99") (pin "1") (pinfunction "1_1") (pintype "passive"))
    )
    (net (code "295") (name "/NEW_294") (class "Default")
      (node (ref "JP100") (pin "5") (pinfunction "5_5") (pintype "passive"))
      (node (ref "JP16") (pin "15") (pinfunction "15_15") (pintype "passive"))
    )
    (net (code "296") (name "/NEW_295") (class "Default")
      (node (ref "JP100") (pin "4") (pinfunction "4_4") (pintype "passive"))
      (node (ref "JP16") (pin "14") (pinfunction "14_14") (pintype "passive"))
    )
    (net (code "297") (name "/NEW_296") (class "Default")
      (node (ref "JP100") (pin "3") (pinfunction "3_3") (pintype "passive"))
      (node (ref "JP16") (pin "13") (pinfunction "13_13") (pintype "passive"))
    )
    (net (code "298") (name "/NEW_297") (class "Default")
      (node (ref "JP100") (pin "2") (pinfunction "2_2") (pintype "passive"))
      (node (ref "JP16") (pin "12") (pinfunction "12_12") (pintype "passive"))
    )
    (net (code "299") (name "/NEW_298") (class "Default")
      (node (ref "JP100") (pin "1") (pinfunction "1_1") (pintype "passive"))
      (node (ref "JP16") (pin "11") (pinfunction "11_11") (pintype "passive"))
    )
    (net (code "300") (name "/NEW_300") (class "Default")
      (node (ref "JP13") (pin "15") (pinfunction "15_15") (pintype "passive"))
      (node (ref "JP64") (pin "4") (pinfunction "4_4") (pintype "passive"))
    )
  )
)
